# IRIS2_PCB_CPU.net
KiCad netlist of a schematic drawn in Altium Designer
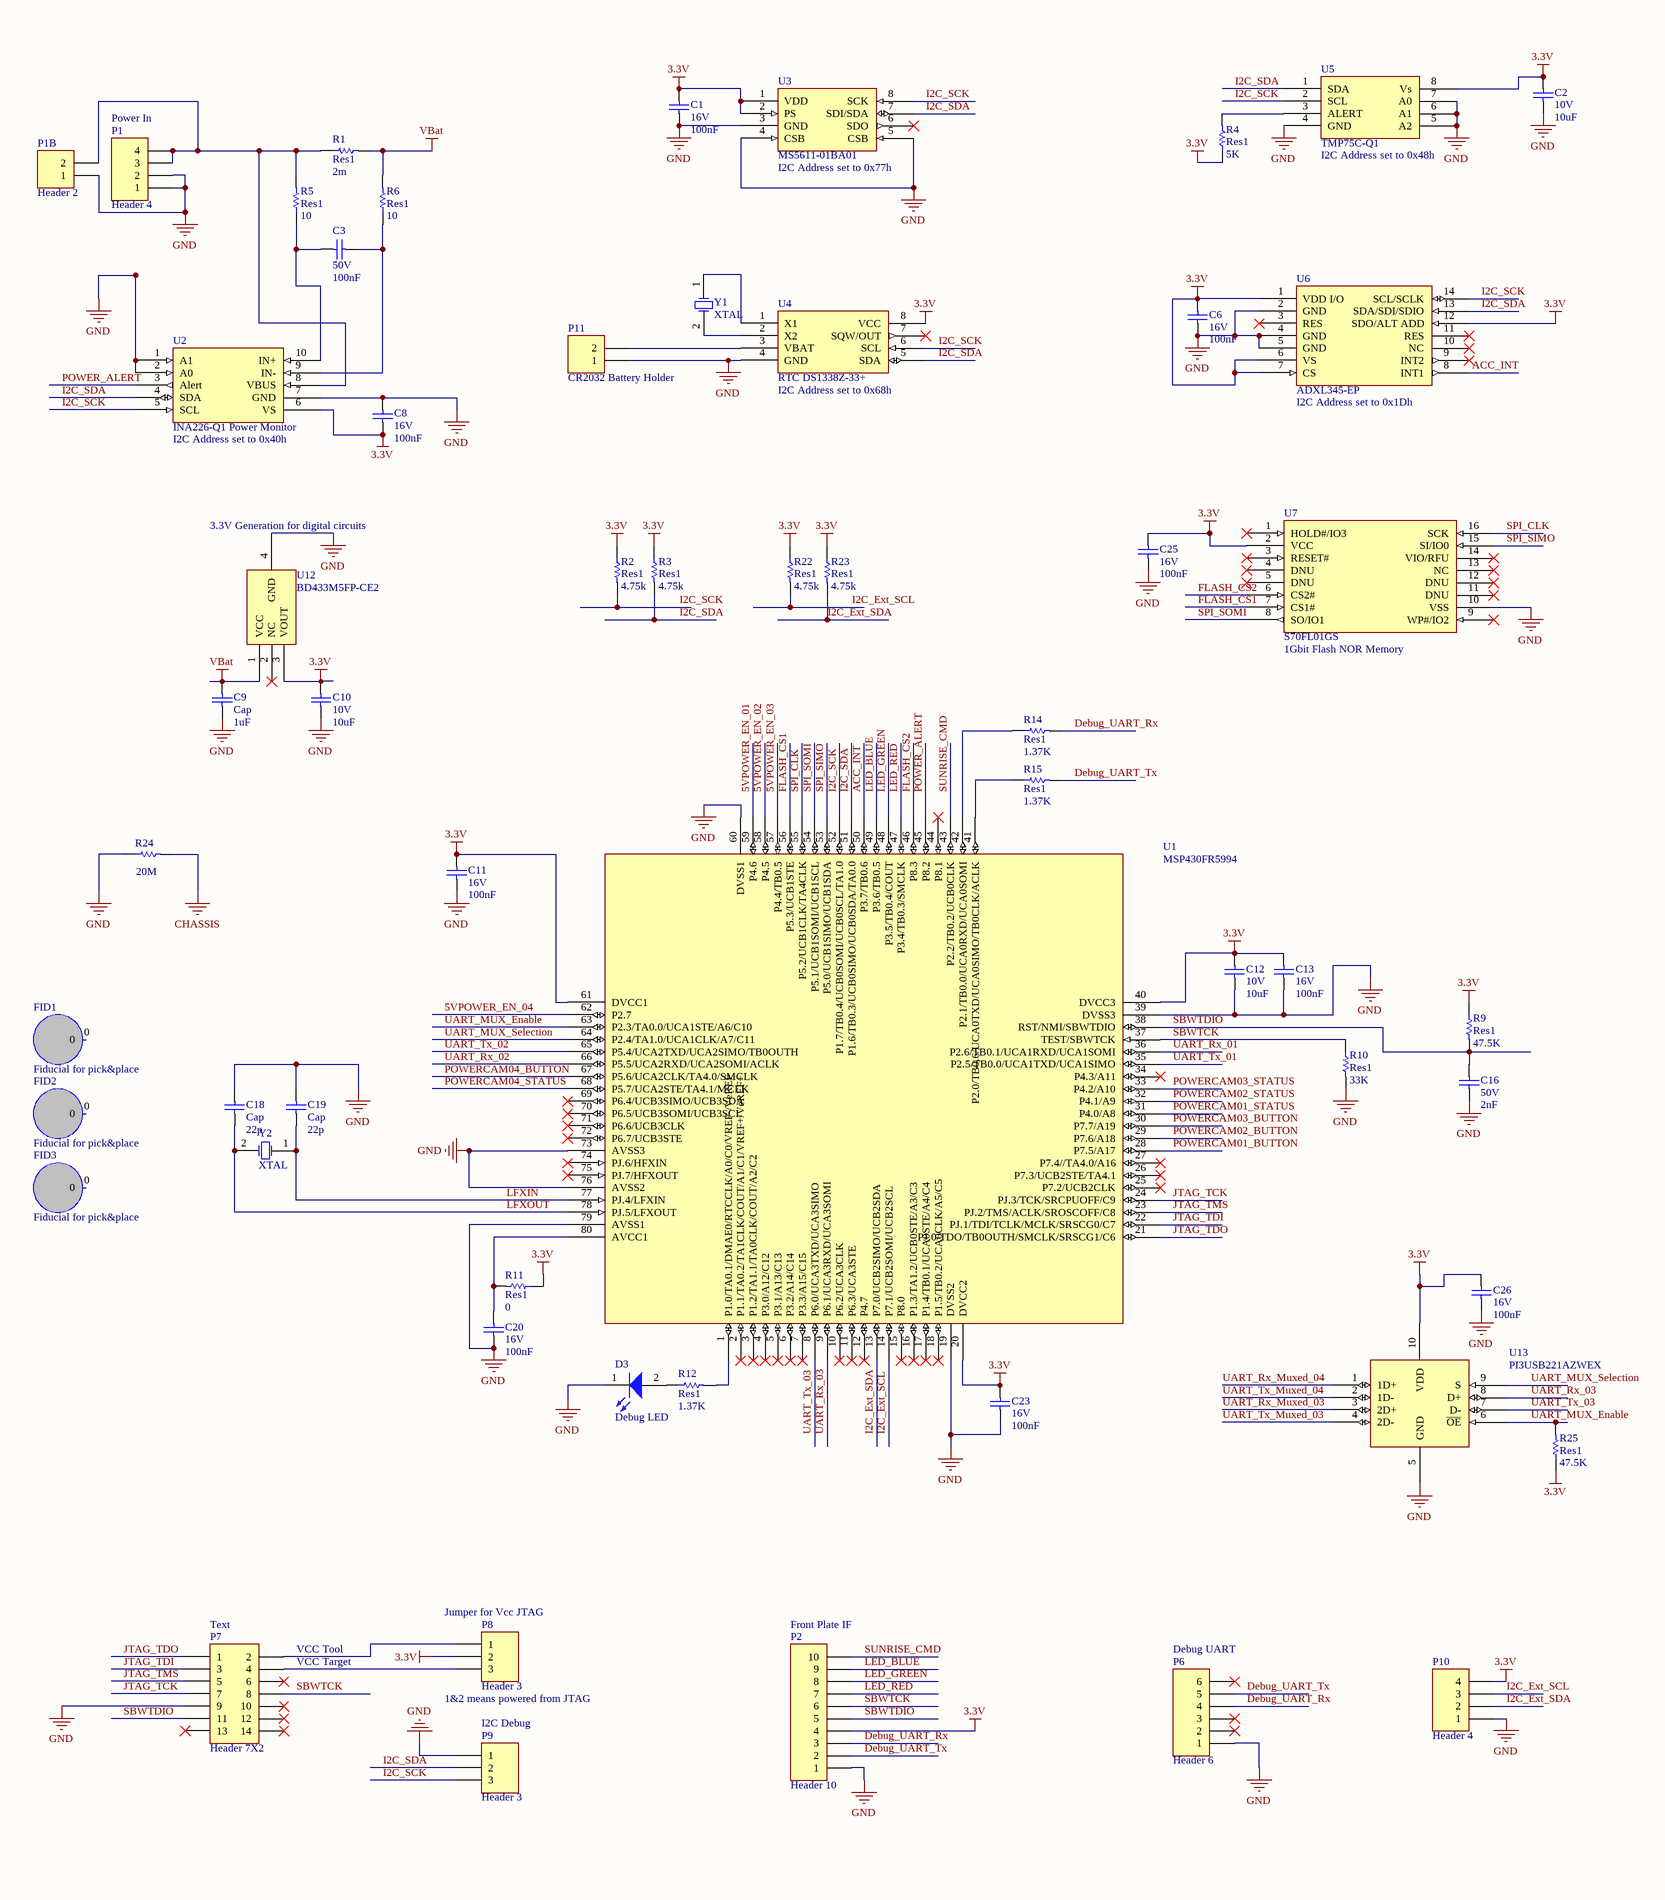
[diagram p0: IRIS2_PCB_CPU.SchDoc, left]
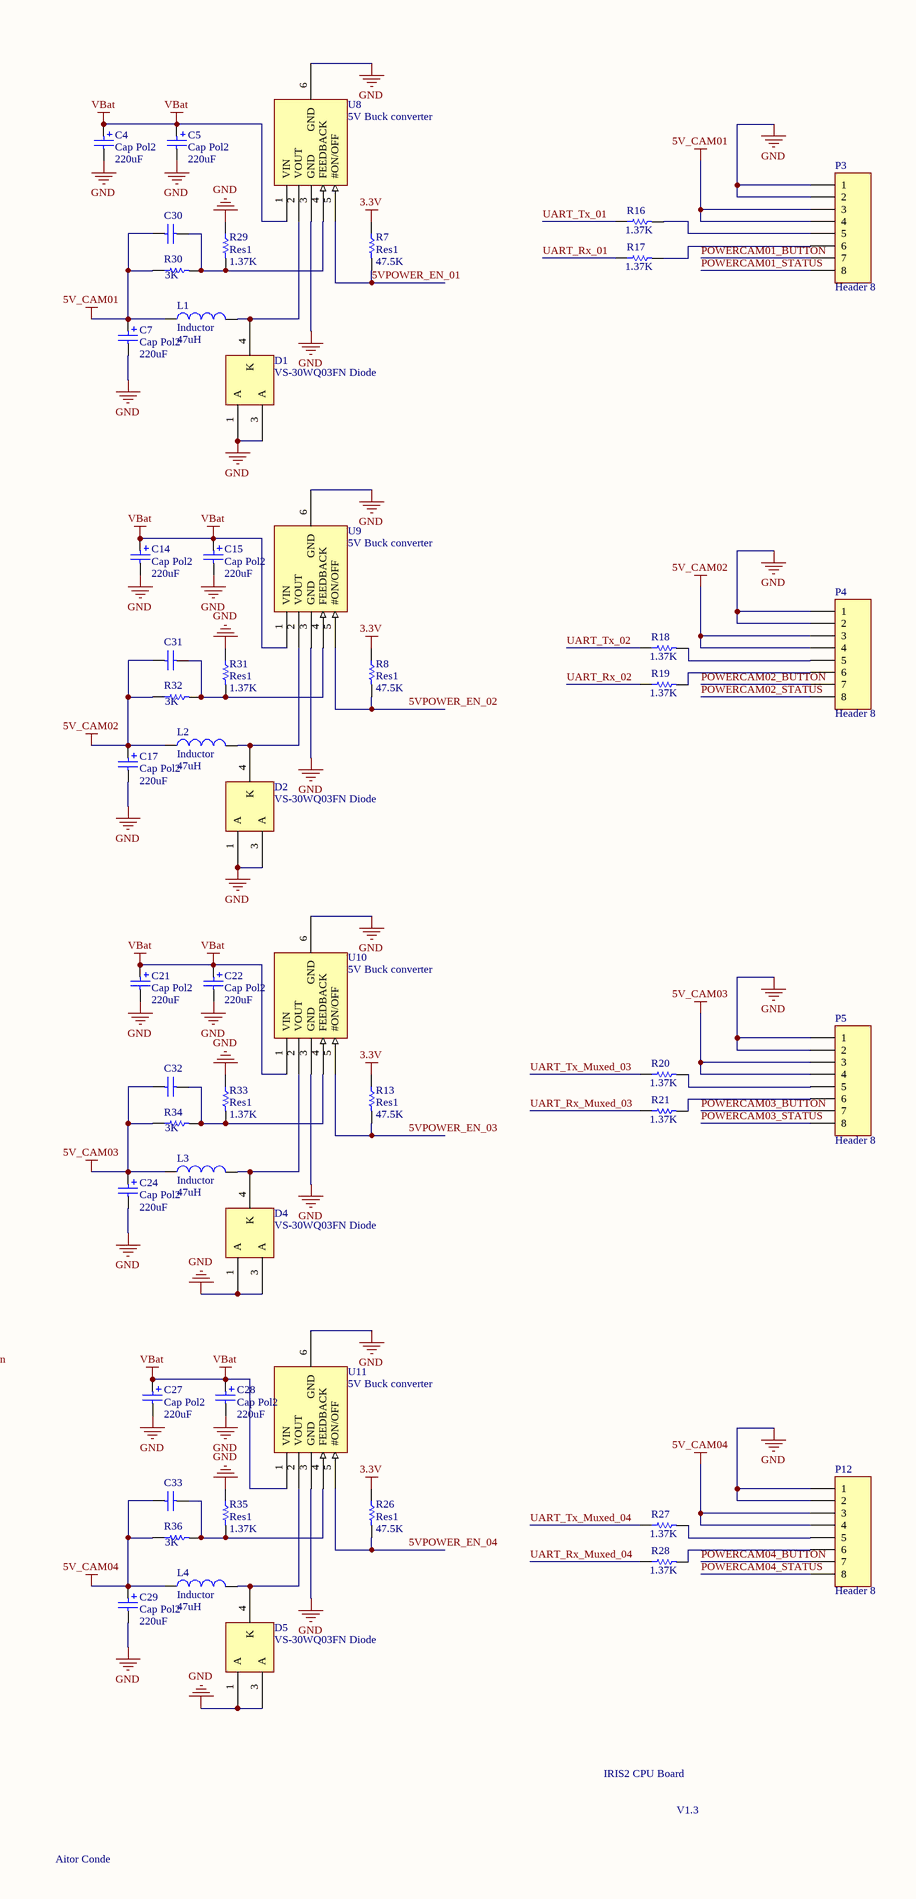
[diagram p1: IRIS2_PCB_CPU.SchDoc, right]

(export (version "E")
  (design (tool "Eeschema 10.0.6"))
  (components
    (comp (ref "C1")
      (value "16V")
      (footprint "0402")
      (description "Capacitor")
      (fields
        (field (name "ALTIUM_VALUE") "100nF")
        (field (name "MANUFACTURER") "Murata")
        (field (name "PUBLISHER") "Altium Limited")
      )
      (libsource (lib "Miscellaneous Devices") (part "Cap"))
    )
    (comp (ref "C2")
      (value "10V")
      (footprint "1608[0603]")
      (description "Capacitor")
      (fields
        (field (name "ALTIUM_VALUE") "10uF")
        (field (name "MANUFACTURER") "Murata")
        (field (name "PUBLISHER") "Altium Limited")
      )
      (libsource (lib "Miscellaneous Devices") (part "Cap"))
    )
    (comp (ref "C3")
      (value "50V")
      (footprint "6-0805_L")
      (description "Capacitor")
      (fields
        (field (name "ALTIUM_VALUE") "100nF")
        (field (name "MANUFACTURER") "Murata")
        (field (name "PUBLISHER") "Altium Limited")
      )
      (libsource (lib "Miscellaneous Devices") (part "Cap"))
    )
    (comp (ref "C4")
      (value "Cap Pol2")
      (footprint "2917 [7343 Metric]")
      (description "Polarized Capacitor (Axial)")
      (fields (field (name "ALTIUM_VALUE") "220uF") (field (name "MANUFACTURER") "Kemet"))
      (libsource (lib "Miscellaneous Devices") (part "Cap Pol2"))
    )
    (comp (ref "C5")
      (value "Cap Pol2")
      (footprint "2917 [7343 Metric]")
      (description "Polarized Capacitor (Axial)")
      (fields (field (name "ALTIUM_VALUE") "220uF") (field (name "MANUFACTURER") "Kemet"))
      (libsource (lib "Miscellaneous Devices") (part "Cap Pol2"))
    )
    (comp (ref "C6")
      (value "16V")
      (footprint "0402")
      (description "Capacitor")
      (fields
        (field (name "ALTIUM_VALUE") "100nF")
        (field (name "MANUFACTURER") "Murata")
        (field (name "PUBLISHER") "Altium Limited")
      )
      (libsource (lib "Miscellaneous Devices") (part "Cap"))
    )
    (comp (ref "C7")
      (value "Cap Pol2")
      (footprint "2917 [7343 Metric]")
      (description "Polarized Capacitor (Axial)")
      (fields (field (name "ALTIUM_VALUE") "220uF") (field (name "MANUFACTURER") "Kemet"))
      (libsource (lib "Miscellaneous Devices") (part "Cap Pol2"))
    )
    (comp (ref "C8")
      (value "16V")
      (footprint "0402")
      (description "Capacitor")
      (fields
        (field (name "ALTIUM_VALUE") "100nF")
        (field (name "MANUFACTURER") "Murata")
        (field (name "PUBLISHER") "Altium Limited")
      )
      (libsource (lib "Miscellaneous Devices") (part "Cap"))
    )
    (comp (ref "C9")
      (value "Cap")
      (footprint "1608[0603]")
      (description "Capacitor")
      (fields
        (field (name "MANUFACTURER") "Murata")
        (field (name "ALTIUM_VALUE") "1uF")
        (field (name "PUBLISHER") "Altium Limited")
      )
      (libsource (lib "Miscellaneous Devices") (part "Cap"))
    )
    (comp (ref "C10")
      (value "10V")
      (footprint "1608[0603]")
      (description "Capacitor")
      (fields
        (field (name "ALTIUM_VALUE") "10uF")
        (field (name "MANUFACTURER") "Murata")
        (field (name "PUBLISHER") "Altium Limited")
      )
      (libsource (lib "Miscellaneous Devices") (part "Cap"))
    )
    (comp (ref "C11")
      (value "16V")
      (footprint "0402")
      (description "Capacitor")
      (fields
        (field (name "ALTIUM_VALUE") "100nF")
        (field (name "MANUFACTURER") "Murata")
        (field (name "PUBLISHER") "Altium Limited")
      )
      (libsource (lib "Miscellaneous Devices") (part "Cap"))
    )
    (comp (ref "C12")
      (value "10V")
      (footprint "1608[0603]")
      (description "Capacitor")
      (fields
        (field (name "ALTIUM_VALUE") "10uF")
        (field (name "MANUFACTURER") "Murata")
        (field (name "PUBLISHER") "Altium Limited")
      )
      (libsource (lib "Miscellaneous Devices") (part "Cap"))
    )
    (comp (ref "C13")
      (value "16V")
      (footprint "0402")
      (description "Capacitor")
      (fields
        (field (name "ALTIUM_VALUE") "100nF")
        (field (name "MANUFACTURER") "Murata")
        (field (name "PUBLISHER") "Altium Limited")
      )
      (libsource (lib "Miscellaneous Devices") (part "Cap"))
    )
    (comp (ref "C14")
      (value "Cap Pol2")
      (footprint "2917 [7343 Metric]")
      (description "Polarized Capacitor (Axial)")
      (fields (field (name "ALTIUM_VALUE") "220uF") (field (name "MANUFACTURER") "Kemet"))
      (libsource (lib "Miscellaneous Devices") (part "Cap Pol2"))
    )
    (comp (ref "C15")
      (value "Cap Pol2")
      (footprint "2917 [7343 Metric]")
      (description "Polarized Capacitor (Axial)")
      (fields (field (name "ALTIUM_VALUE") "220uF") (field (name "MANUFACTURER") "Kemet"))
      (libsource (lib "Miscellaneous Devices") (part "Cap Pol2"))
    )
    (comp (ref "C16")
      (value "50V")
      (footprint "0402")
      (description "Capacitor")
      (fields
        (field (name "ALTIUM_VALUE") "2nF")
        (field (name "MANUFACTURER") "Murata")
        (field (name "PUBLISHER") "Altium Limited")
      )
      (libsource (lib "Miscellaneous Devices") (part "Cap"))
    )
    (comp (ref "C17")
      (value "Cap Pol2")
      (footprint "2917 [7343 Metric]")
      (description "Polarized Capacitor (Axial)")
      (fields (field (name "ALTIUM_VALUE") "220uF") (field (name "MANUFACTURER") "Kemet"))
      (libsource (lib "Miscellaneous Devices") (part "Cap Pol2"))
    )
    (comp (ref "C18")
      (value "Cap")
      (footprint "0402")
      (description "Capacitor")
      (fields
        (field (name "MANUFACTURER") "Murata")
        (field (name "ALTIUM_VALUE") "22p")
        (field (name "PUBLISHER") "Altium Limited")
      )
      (libsource (lib "Miscellaneous Devices") (part "Cap"))
    )
    (comp (ref "C19")
      (value "Cap")
      (footprint "0402")
      (description "Capacitor")
      (fields
        (field (name "MANUFACTURER") "Murata")
        (field (name "ALTIUM_VALUE") "22p")
        (field (name "PUBLISHER") "Altium Limited")
      )
      (libsource (lib "Miscellaneous Devices") (part "Cap"))
    )
    (comp (ref "C20")
      (value "16V")
      (footprint "0402")
      (description "Capacitor")
      (fields
        (field (name "ALTIUM_VALUE") "100nF")
        (field (name "MANUFACTURER") "Murata")
        (field (name "PUBLISHER") "Altium Limited")
      )
      (libsource (lib "Miscellaneous Devices") (part "Cap"))
    )
    (comp (ref "C21")
      (value "Cap Pol2")
      (footprint "2917 [7343 Metric]")
      (description "Polarized Capacitor (Axial)")
      (fields (field (name "ALTIUM_VALUE") "220uF") (field (name "MANUFACTURER") "Kemet"))
      (libsource (lib "Miscellaneous Devices") (part "Cap Pol2"))
    )
    (comp (ref "C22")
      (value "Cap Pol2")
      (footprint "2917 [7343 Metric]")
      (description "Polarized Capacitor (Axial)")
      (fields (field (name "ALTIUM_VALUE") "220uF") (field (name "MANUFACTURER") "Kemet"))
      (libsource (lib "Miscellaneous Devices") (part "Cap Pol2"))
    )
    (comp (ref "C23")
      (value "16V")
      (footprint "0402")
      (description "Capacitor")
      (fields
        (field (name "ALTIUM_VALUE") "100nF")
        (field (name "MANUFACTURER") "Murata")
        (field (name "PUBLISHER") "Altium Limited")
      )
      (libsource (lib "Miscellaneous Devices") (part "Cap"))
    )
    (comp (ref "C24")
      (value "Cap Pol2")
      (footprint "2917 [7343 Metric]")
      (description "Polarized Capacitor (Axial)")
      (fields (field (name "ALTIUM_VALUE") "220uF") (field (name "MANUFACTURER") "Kemet"))
      (libsource (lib "Miscellaneous Devices") (part "Cap Pol2"))
    )
    (comp (ref "C25")
      (value "16V")
      (footprint "0402")
      (description "Capacitor")
      (fields
        (field (name "ALTIUM_VALUE") "100nF")
        (field (name "MANUFACTURER") "Murata")
        (field (name "PUBLISHER") "Altium Limited")
      )
      (libsource (lib "Miscellaneous Devices") (part "Cap"))
    )
    (comp (ref "C26")
      (value "16V")
      (footprint "0402")
      (description "Capacitor")
      (fields
        (field (name "ALTIUM_VALUE") "100nF")
        (field (name "MANUFACTURER") "Murata")
        (field (name "PUBLISHER") "Altium Limited")
      )
      (libsource (lib "Miscellaneous Devices") (part "Cap"))
    )
    (comp (ref "C27")
      (value "Cap Pol2")
      (footprint "2917 [7343 Metric]")
      (description "Polarized Capacitor (Axial)")
      (fields (field (name "ALTIUM_VALUE") "220uF") (field (name "MANUFACTURER") "Kemet"))
      (libsource (lib "Miscellaneous Devices") (part "Cap Pol2"))
    )
    (comp (ref "C28")
      (value "Cap Pol2")
      (footprint "2917 [7343 Metric]")
      (description "Polarized Capacitor (Axial)")
      (fields (field (name "ALTIUM_VALUE") "220uF") (field (name "MANUFACTURER") "Kemet"))
      (libsource (lib "Miscellaneous Devices") (part "Cap Pol2"))
    )
    (comp (ref "C29")
      (value "Cap Pol2")
      (footprint "2917 [7343 Metric]")
      (description "Polarized Capacitor (Axial)")
      (fields (field (name "ALTIUM_VALUE") "220uF") (field (name "MANUFACTURER") "Kemet"))
      (libsource (lib "Miscellaneous Devices") (part "Cap Pol2"))
    )
    (comp (ref "C30")
      (value "16V")
      (footprint "0402")
      (description "Capacitor")
      (fields (field (name "PUBLISHER") "Altium Limited"))
      (libsource (lib "Miscellaneous Devices") (part "Cap"))
    )
    (comp (ref "C31")
      (value "16V")
      (footprint "0402")
      (description "Capacitor")
      (fields (field (name "PUBLISHER") "Altium Limited"))
      (libsource (lib "Miscellaneous Devices") (part "Cap"))
    )
    (comp (ref "C32")
      (value "16V")
      (footprint "0402")
      (description "Capacitor")
      (fields (field (name "PUBLISHER") "Altium Limited"))
      (libsource (lib "Miscellaneous Devices") (part "Cap"))
    )
    (comp (ref "C33")
      (value "16V")
      (footprint "0402")
      (description "Capacitor")
      (fields (field (name "PUBLISHER") "Altium Limited"))
      (libsource (lib "Miscellaneous Devices") (part "Cap"))
    )
    (comp (ref "D1")
      (value "VS-30WQ03FN Diode")
      (footprint "VS-30WQ03FN")
      (fields (field (name "MANUFACTURER") "Vishay"))
      (libsource (lib "Diode_VS-30WQ03FN") (part "VS-30WQ03FN"))
    )
    (comp (ref "D2")
      (value "VS-30WQ03FN Diode")
      (footprint "VS-30WQ03FN")
      (fields (field (name "MANUFACTURER") "Vishay"))
      (libsource (lib "Diode_VS-30WQ03FN") (part "VS-30WQ03FN"))
    )
    (comp (ref "D3")
      (value "Debug LED")
      (footprint "0402-A")
      (description "Typical RED, GREEN, YELLOW, AMBER GaAs LED")
      (fields (field (name "MANUFACTURER") "ROHM Semiconductor") (field (name "PUBLISHER") "Altium Limited"))
      (libsource (lib "Miscellaneous Devices") (part "LED2"))
    )
    (comp (ref "D4")
      (value "VS-30WQ03FN Diode")
      (footprint "VS-30WQ03FN")
      (fields (field (name "MANUFACTURER") "Vishay"))
      (libsource (lib "Diode_VS-30WQ03FN") (part "VS-30WQ03FN"))
    )
    (comp (ref "D5")
      (value "VS-30WQ03FN Diode")
      (footprint "VS-30WQ03FN")
      (fields (field (name "MANUFACTURER") "Vishay"))
      (libsource (lib "Diode_VS-30WQ03FN") (part "VS-30WQ03FN"))
    )
    (comp (ref "FID1")
      (value "Fiducial for pick&place")
      (footprint "FiducialPoint")
      (libsource (lib "FiducialPoint") (part "Fiducial"))
    )
    (comp (ref "FID2")
      (value "Fiducial for pick&place")
      (footprint "FiducialPoint")
      (libsource (lib "FiducialPoint") (part "Fiducial"))
    )
    (comp (ref "FID3")
      (value "Fiducial for pick&place")
      (footprint "FiducialPoint")
      (libsource (lib "FiducialPoint") (part "Fiducial"))
    )
    (comp (ref "L1")
      (value "Inductor")
      (footprint "DO5022P-473MLB")
      (fields (field (name "ALTIUM_VALUE") "47uH") (field (name "MANUFACTURER") "Coilcraft"))
      (libsource (lib "Miscellaneous Devices") (part "Inductor"))
    )
    (comp (ref "L2")
      (value "Inductor")
      (footprint "DO5022P-473MLB")
      (fields (field (name "ALTIUM_VALUE") "47uH") (field (name "MANUFACTURER") "Coilcraft"))
      (libsource (lib "Miscellaneous Devices") (part "Inductor"))
    )
    (comp (ref "L3")
      (value "Inductor")
      (footprint "DO5022P-473MLB")
      (fields (field (name "ALTIUM_VALUE") "47uH") (field (name "MANUFACTURER") "Coilcraft"))
      (libsource (lib "Miscellaneous Devices") (part "Inductor"))
    )
    (comp (ref "L4")
      (value "Inductor")
      (footprint "DO5022P-473MLB")
      (fields (field (name "ALTIUM_VALUE") "47uH") (field (name "MANUFACTURER") "Coilcraft"))
      (libsource (lib "Miscellaneous Devices") (part "Inductor"))
    )
    (comp (ref "P1")
      (value "Header 4")
      (footprint "53047-0410")
      (description "Header, 4-Pin")
      (fields (field (name "MANUFACTURER") "Molex") (field (name "PUBLISHER") "Altium Limited"))
      (libsource (lib "Miscellaneous Connectors") (part "Header 4"))
    )
    (comp (ref "P1B")
      (value "Header 2")
      (footprint "HDR1X2")
      (description "Header, 2-Pin")
      (fields (field (name "PUBLISHER") "Altium Limited"))
      (libsource (lib "Miscellaneous Connectors") (part "Header 2"))
    )
    (comp (ref "P2")
      (value "Header 10")
      (footprint "530471010")
      (description "Header, 10-Pin")
      (fields (field (name "MANUFACTURER") "Molex"))
      (libsource (lib "Miscellaneous Connectors") (part "Header 10"))
    )
    (comp (ref "P3")
      (value "Header 8")
      (footprint "0530470810")
      (description "Header, 8-Pin")
      (fields (field (name "MANUFACTURER") "Molex"))
      (libsource (lib "Miscellaneous Connectors") (part "Header 8"))
    )
    (comp (ref "P4")
      (value "Header 8")
      (footprint "0530470810")
      (description "Header, 8-Pin")
      (fields (field (name "MANUFACTURER") "Molex"))
      (libsource (lib "Miscellaneous Connectors") (part "Header 8"))
    )
    (comp (ref "P5")
      (value "Header 8")
      (footprint "0530470810")
      (description "Header, 8-Pin")
      (fields (field (name "MANUFACTURER") "Molex"))
      (libsource (lib "Miscellaneous Connectors") (part "Header 8"))
    )
    (comp (ref "P6")
      (value "Header 6")
      (footprint "HDR1X6")
      (description "Header, 6-Pin")
      (fields (field (name "PUBLISHER") "Altium Limited"))
      (libsource (lib "Miscellaneous Connectors") (part "Header 6"))
    )
    (comp (ref "P7")
      (value "Header 7X2")
      (footprint "HDR2X7")
      (description "Header, 7-Pin, Dual row")
      (fields (field (name "PUBLISHER") "Altium Limited"))
      (libsource (lib "Miscellaneous Connectors") (part "Header 7X2"))
    )
    (comp (ref "P8")
      (value "Header 3")
      (footprint "HDR1X3")
      (description "Header, 3-Pin")
      (fields (field (name "PUBLISHER") "Altium Limited"))
      (libsource (lib "Miscellaneous Connectors") (part "Header 3"))
    )
    (comp (ref "P9")
      (value "Header 3")
      (footprint "HDR1X3")
      (description "Header, 3-Pin")
      (fields (field (name "PUBLISHER") "Altium Limited"))
      (libsource (lib "Miscellaneous Connectors") (part "Header 3"))
    )
    (comp (ref "P10")
      (value "Header 4")
      (footprint "53047-0410")
      (description "Header, 4-Pin")
      (fields (field (name "MANUFACTURER") "Molex") (field (name "PUBLISHER") "Altium Limited"))
      (libsource (lib "Miscellaneous Connectors") (part "Header 4"))
    )
    (comp (ref "P11")
      (value "CR2032 Battery Holder")
      (footprint "SMTU2032-LF")
      (fields (field (name "MANUFACTURER") "Renata"))
      (libsource (lib "Miscellaneous Connectors") (part "Header 2"))
    )
    (comp (ref "P12")
      (value "Header 8")
      (footprint "0530470810")
      (description "Header, 8-Pin")
      (fields (field (name "MANUFACTURER") "Molex"))
      (libsource (lib "Miscellaneous Connectors") (part "Header 8"))
    )
    (comp (ref "R1")
      (value "Res1")
      (footprint "INDC3216")
      (description "Resistor")
      (fields
        (field (name "ALTIUM_VALUE") "2m")
        (field (name "MANUFACTURER") "ROHM Semiconductor")
        (field (name "SPPLIER PART NUMBER") "755-PMR18EZPFV2L00")
        (field (name "PUBLISHER") "Altium Limited")
      )
      (libsource (lib "Miscellaneous Devices") (part "Res1"))
    )
    (comp (ref "R2")
      (value "Res1")
      (footprint "0402")
      (description "Resistor")
      (fields
        (field (name "MANUFACTURER") "Panasonic")
        (field (name "ALTIUM_VALUE") "4.75k")
        (field (name "PUBLISHER") "Altium Limited")
      )
      (libsource (lib "Miscellaneous Devices") (part "Res1"))
    )
    (comp (ref "R3")
      (value "Res1")
      (footprint "0402")
      (description "Resistor")
      (fields
        (field (name "MANUFACTURER") "Panasonic")
        (field (name "ALTIUM_VALUE") "4.75k")
        (field (name "PUBLISHER") "Altium Limited")
      )
      (libsource (lib "Miscellaneous Devices") (part "Res1"))
    )
    (comp (ref "R4")
      (value "Res1")
      (footprint "0402")
      (description "Resistor")
      (fields
        (field (name "ALTIUM_VALUE") "5K")
        (field (name "MANUFACTURER") "Yageo")
        (field (name "PUBLISHER") "Altium Limited")
      )
      (libsource (lib "Miscellaneous Devices") (part "Res1"))
    )
    (comp (ref "R5")
      (value "Res1")
      (footprint "0402")
      (description "Resistor")
      (fields
        (field (name "MANUFACTURER") "Panasonic")
        (field (name "ALTIUM_VALUE") "10")
        (field (name "PUBLISHER") "Altium Limited")
      )
      (libsource (lib "Miscellaneous Devices") (part "Res1"))
    )
    (comp (ref "R6")
      (value "Res1")
      (footprint "0402")
      (description "Resistor")
      (fields
        (field (name "MANUFACTURER") "Panasonic")
        (field (name "ALTIUM_VALUE") "10")
        (field (name "PUBLISHER") "Altium Limited")
      )
      (libsource (lib "Miscellaneous Devices") (part "Res1"))
    )
    (comp (ref "R7")
      (value "Res1")
      (footprint "0402")
      (description "Resistor")
      (fields (field (name "ALTIUM_VALUE") "47.5K") (field (name "MANUFACTURER") "Panasonic"))
      (libsource (lib "Miscellaneous Devices") (part "Res1"))
    )
    (comp (ref "R8")
      (value "Res1")
      (footprint "0402")
      (description "Resistor")
      (fields (field (name "ALTIUM_VALUE") "47.5K") (field (name "MANUFACTURER") "Panasonic"))
      (libsource (lib "Miscellaneous Devices") (part "Res1"))
    )
    (comp (ref "R9")
      (value "Res1")
      (footprint "0402")
      (description "Resistor")
      (fields (field (name "ALTIUM_VALUE") "47.5K") (field (name "MANUFACTURER") "Panasonic"))
      (libsource (lib "Miscellaneous Devices") (part "Res1"))
    )
    (comp (ref "R10")
      (value "Res1")
      (footprint "0402")
      (description "Resistor")
      (fields
        (field (name "ALTIUM_VALUE") "33K")
        (field (name "MANUFACTURER") "Panasonic")
        (field (name "PUBLISHER") "Altium Limited")
      )
      (libsource (lib "Miscellaneous Devices") (part "Res1"))
    )
    (comp (ref "R11")
      (value "Res1")
      (footprint "J1-0603")
      (description "Resistor")
      (fields
        (field (name "ALTIUM_VALUE") "0")
        (field (name "MANUFACTURER") "Panasonic")
        (field (name "PUBLISHER") "Altium Limited")
      )
      (libsource (lib "Miscellaneous Devices") (part "Res1"))
    )
    (comp (ref "R12")
      (value "Res1")
      (footprint "0402")
      (description "Resistor")
      (fields
        (field (name "MANUFACTURER") "Panasonic")
        (field (name "ALTIUM_VALUE") "1.37K")
        (field (name "PUBLISHER") "Altium Limited")
      )
      (libsource (lib "Miscellaneous Devices") (part "Res1"))
    )
    (comp (ref "R13")
      (value "Res1")
      (footprint "0402")
      (description "Resistor")
      (fields (field (name "ALTIUM_VALUE") "47.5K") (field (name "MANUFACTURER") "Panasonic"))
      (libsource (lib "Miscellaneous Devices") (part "Res1"))
    )
    (comp (ref "R14")
      (value "Res1")
      (footprint "0402")
      (description "Resistor")
      (fields
        (field (name "MANUFACTURER") "Panasonic")
        (field (name "ALTIUM_VALUE") "1.37K")
        (field (name "PUBLISHER") "Altium Limited")
      )
      (libsource (lib "Miscellaneous Devices") (part "Res1"))
    )
    (comp (ref "R15")
      (value "Res1")
      (footprint "0402")
      (description "Resistor")
      (fields
        (field (name "MANUFACTURER") "Panasonic")
        (field (name "ALTIUM_VALUE") "1.37K")
        (field (name "PUBLISHER") "Altium Limited")
      )
      (libsource (lib "Miscellaneous Devices") (part "Res1"))
    )
    (comp (ref "R16")
      (value "1.37K")
      (footprint "0402")
      (description "Resistor")
      (fields
        (field (name "MANUFACTURER") "Panasonic")
        (field (name "Comment") "Res1")
        (field (name "PUBLISHER") "Altium Limited")
      )
      (libsource (lib "Miscellaneous Devices") (part "Res1"))
    )
    (comp (ref "R17")
      (value "1.37K")
      (footprint "0402")
      (description "Resistor")
      (fields
        (field (name "MANUFACTURER") "Panasonic")
        (field (name "Comment") "Res1")
        (field (name "PUBLISHER") "Altium Limited")
      )
      (libsource (lib "Miscellaneous Devices") (part "Res1"))
    )
    (comp (ref "R18")
      (value "1.37K")
      (footprint "0402")
      (description "Resistor")
      (fields
        (field (name "MANUFACTURER") "Panasonic")
        (field (name "Comment") "Res1")
        (field (name "PUBLISHER") "Altium Limited")
      )
      (libsource (lib "Miscellaneous Devices") (part "Res1"))
    )
    (comp (ref "R19")
      (value "1.37K")
      (footprint "0402")
      (description "Resistor")
      (fields
        (field (name "MANUFACTURER") "Panasonic")
        (field (name "Comment") "Res1")
        (field (name "PUBLISHER") "Altium Limited")
      )
      (libsource (lib "Miscellaneous Devices") (part "Res1"))
    )
    (comp (ref "R20")
      (value "1.37K")
      (footprint "0402")
      (description "Resistor")
      (fields
        (field (name "MANUFACTURER") "Panasonic")
        (field (name "Comment") "Res1")
        (field (name "PUBLISHER") "Altium Limited")
      )
      (libsource (lib "Miscellaneous Devices") (part "Res1"))
    )
    (comp (ref "R21")
      (value "1.37K")
      (footprint "0402")
      (description "Resistor")
      (fields
        (field (name "MANUFACTURER") "Panasonic")
        (field (name "Comment") "Res1")
        (field (name "PUBLISHER") "Altium Limited")
      )
      (libsource (lib "Miscellaneous Devices") (part "Res1"))
    )
    (comp (ref "R22")
      (value "Res1")
      (footprint "0402")
      (description "Resistor")
      (fields
        (field (name "MANUFACTURER") "Panasonic")
        (field (name "ALTIUM_VALUE") "4.75k")
        (field (name "PUBLISHER") "Altium Limited")
      )
      (libsource (lib "Miscellaneous Devices") (part "Res1"))
    )
    (comp (ref "R23")
      (value "Res1")
      (footprint "0402")
      (description "Resistor")
      (fields
        (field (name "MANUFACTURER") "Panasonic")
        (field (name "ALTIUM_VALUE") "4.75k")
        (field (name "PUBLISHER") "Altium Limited")
      )
      (libsource (lib "Miscellaneous Devices") (part "Res1"))
    )
    (comp (ref "R24")
      (value "20M")
      (footprint "6-0805_N")
      (description "Resistor")
      (fields
        (field (name "MANUFACTURER") "KOA")
        (field (name "Comment") "Res1")
        (field (name "PUBLISHER") "Altium Limited")
      )
      (libsource (lib "Miscellaneous Devices") (part "Res1"))
    )
    (comp (ref "R25")
      (value "Res1")
      (footprint "0402")
      (description "Resistor")
      (fields (field (name "ALTIUM_VALUE") "47.5K") (field (name "MANUFACTURER") "Panasonic"))
      (libsource (lib "Miscellaneous Devices") (part "Res1"))
    )
    (comp (ref "R26")
      (value "Res1")
      (footprint "0402")
      (description "Resistor")
      (fields (field (name "ALTIUM_VALUE") "47.5K") (field (name "MANUFACTURER") "Panasonic"))
      (libsource (lib "Miscellaneous Devices") (part "Res1"))
    )
    (comp (ref "R27")
      (value "1.37K")
      (footprint "0402")
      (description "Resistor")
      (fields
        (field (name "MANUFACTURER") "Panasonic")
        (field (name "Comment") "Res1")
        (field (name "PUBLISHER") "Altium Limited")
      )
      (libsource (lib "Miscellaneous Devices") (part "Res1"))
    )
    (comp (ref "R28")
      (value "1.37K")
      (footprint "0402")
      (description "Resistor")
      (fields
        (field (name "MANUFACTURER") "Panasonic")
        (field (name "Comment") "Res1")
        (field (name "PUBLISHER") "Altium Limited")
      )
      (libsource (lib "Miscellaneous Devices") (part "Res1"))
    )
    (comp (ref "R29")
      (value "Res1")
      (footprint "0402")
      (description "Resistor")
      (fields
        (field (name "MANUFACTURER") "Panasonic")
        (field (name "ALTIUM_VALUE") "1.37K")
        (field (name "PUBLISHER") "Altium Limited")
      )
      (libsource (lib "Miscellaneous Devices") (part "Res1"))
    )
    (comp (ref "R30")
      (value "3K")
      (footprint "0402")
      (description "Resistor")
      (fields
        (field (name "MANUFACTURER") "Vishay")
        (field (name "Comment") "Res1")
        (field (name "PUBLISHER") "Altium Limited")
      )
      (libsource (lib "Miscellaneous Devices") (part "Res1"))
    )
    (comp (ref "R31")
      (value "Res1")
      (footprint "0402")
      (description "Resistor")
      (fields
        (field (name "MANUFACTURER") "Panasonic")
        (field (name "ALTIUM_VALUE") "1.37K")
        (field (name "PUBLISHER") "Altium Limited")
      )
      (libsource (lib "Miscellaneous Devices") (part "Res1"))
    )
    (comp (ref "R32")
      (value "3K")
      (footprint "0402")
      (description "Resistor")
      (fields
        (field (name "MANUFACTURER") "Vishay")
        (field (name "Comment") "Res1")
        (field (name "PUBLISHER") "Altium Limited")
      )
      (libsource (lib "Miscellaneous Devices") (part "Res1"))
    )
    (comp (ref "R33")
      (value "Res1")
      (footprint "0402")
      (description "Resistor")
      (fields
        (field (name "MANUFACTURER") "Panasonic")
        (field (name "ALTIUM_VALUE") "1.37K")
        (field (name "PUBLISHER") "Altium Limited")
      )
      (libsource (lib "Miscellaneous Devices") (part "Res1"))
    )
    (comp (ref "R34")
      (value "3K")
      (footprint "0402")
      (description "Resistor")
      (fields
        (field (name "MANUFACTURER") "Vishay")
        (field (name "Comment") "Res1")
        (field (name "PUBLISHER") "Altium Limited")
      )
      (libsource (lib "Miscellaneous Devices") (part "Res1"))
    )
    (comp (ref "R35")
      (value "Res1")
      (footprint "0402")
      (description "Resistor")
      (fields
        (field (name "MANUFACTURER") "Panasonic")
        (field (name "ALTIUM_VALUE") "1.37K")
        (field (name "PUBLISHER") "Altium Limited")
      )
      (libsource (lib "Miscellaneous Devices") (part "Res1"))
    )
    (comp (ref "R36")
      (value "3K")
      (footprint "0402")
      (description "Resistor")
      (fields
        (field (name "MANUFACTURER") "Vishay")
        (field (name "Comment") "Res1")
        (field (name "PUBLISHER") "Altium Limited")
      )
      (libsource (lib "Miscellaneous Devices") (part "Res1"))
    )
    (comp (ref "U1")
      (value "MSP430FR5994")
      (footprint "MSP430FR59941PN")
      (description "MSP430FR5994, 80 pin MSP430 FRAM")
      (fields (field (name "MANUFACTURER") "Texas Instruments"))
      (libsource (lib "MSP430FR5994") (part "MSP430FR5994"))
    )
    (comp (ref "U2")
      (value "INA226-Q1 Power Monitor")
      (footprint "INA226-Q1")
      (description "Texas Instruments INA226-Q1 I2C temperature sensor INA226AQDGSRQ1")
      (fields (field (name "MANUFACTURER") "Texas Instruments"))
      (libsource (lib "INA226-Q1") (part "INA226-Q1"))
    )
    (comp (ref "U3")
      (value "MS5611-01BA01")
      (footprint "MS5611-01BA01")
      (description "MS5611-01BA01 Barometric Pressure Sensor")
      (fields (field (name "MANUFACTURER") "measurement specialties"))
      (libsource (lib "MS5611-01BA01") (part "MS5611-01BA01"))
    )
    (comp (ref "U4")
      (value "RTC DS1338Z-33+")
      (footprint "DS1338Z-33+")
      (description "RTC I2C DS1338Z-33+ SOIC-8")
      (fields (field (name "MANUFACTURER") "Maxim Integrated"))
      (libsource (lib "RTC_DS1338Z-33+") (part "DS1338Z-33+"))
    )
    (comp (ref "U5")
      (value "TMP75C-Q1")
      (footprint "TMP75C-Q1")
      (fields (field (name "MANUFACTURER") "Texas Instruments"))
      (libsource (lib "TMP75C-Q1") (part "TMP75C-Q1"))
    )
    (comp (ref "U6")
      (value "ADXL345-EP")
      (footprint "ADXL345-EP")
      (description "ADXL345-EP I2C Accelerometer")
      (fields (field (name "MANUFACTURER") "Analog Devices"))
      (libsource (lib "ADXL345-EP") (part "ADXL345-EP"))
    )
    (comp (ref "U7")
      (value "S70FL01GS")
      (footprint "SPIFlash_S70FL01GSAGMFV010")
      (description "S70FL01GS SPI NOR Flash")
      (fields (field (name "MANUFACTURER") "Cypress"))
      (libsource (lib "SPIFlash_S70FL01GSAGMFV010") (part "S70FL01GS"))
    )
    (comp (ref "U8")
      (value "5V Buck converter")
      (footprint "DPAK170P1435X457-6N")
      (description "LM2596S-5.0/NOPB 5V Buck converter")
      (fields (field (name "MANUFACTURER") "Texas Instruments"))
      (libsource (lib "LM2596S-5.0") (part "LM2596S-5.0/NOPB"))
    )
    (comp (ref "U9")
      (value "5V Buck converter")
      (footprint "DPAK170P1435X457-6N")
      (description "LM2596S-5.0/NOPB 5V Buck converter")
      (fields (field (name "MANUFACTURER") "Texas Instruments"))
      (libsource (lib "LM2596S-5.0") (part "LM2596S-5.0/NOPB"))
    )
    (comp (ref "U10")
      (value "5V Buck converter")
      (footprint "DPAK170P1435X457-6N")
      (description "LM2596S-5.0/NOPB 5V Buck converter")
      (fields (field (name "MANUFACTURER") "Texas Instruments"))
      (libsource (lib "LM2596S-5.0") (part "LM2596S-5.0/NOPB"))
    )
    (comp (ref "U11")
      (value "5V Buck converter")
      (footprint "DPAK170P1435X457-6N")
      (description "LM2596S-5.0/NOPB 5V Buck converter")
      (fields (field (name "MANUFACTURER") "Texas Instruments"))
      (libsource (lib "LM2596S-5.0") (part "LM2596S-5.0/NOPB"))
    )
    (comp (ref "U12")
      (value "BD433M5FP-CE2")
      (footprint "BD433M5FP-CE2")
      (description "BD433M5FP-CE2\r\nLDO 3.3V 500mV")
      (fields (field (name "MANUFACTURER") "ROHM Semiconductor"))
      (libsource (lib "BD433M5FP-CE2") (part "BD433M5FP-CE2"))
    )
    (comp (ref "U13")
      (value "PI3USB221AZWEX")
      (footprint "PI3USB221AZWEX")
      (description "PI3USB221AZWEX Multiplexer")
      (fields (field (name "MANUFACTURER") "Diodes Incorporated"))
      (libsource (lib "Mux_PI3USB221AZWEX") (part "PI3USB221AZWEX"))
    )
    (comp (ref "Y1")
      (value "XTAL")
      (footprint "XTAL_ECS-.327-9-34R-TR")
      (description "Crystal Oscillator")
      (fields (field (name "MANUFACTURER") "ECS"))
      (libsource (lib "Miscellaneous Devices") (part "XTAL"))
    )
    (comp (ref "Y2")
      (value "XTAL")
      (footprint "XTAL_ECS-.327-9-34R-TR")
      (description "Crystal Oscillator")
      (fields (field (name "MANUFACTURER") "ECS"))
      (libsource (lib "Miscellaneous Devices") (part "XTAL"))
    )
  )
  (nets
    (net (code "1") (name "/5VPOWER_EN_01") (class "Default")
      (node (ref "R7") (pin "2") (pinfunction "2_2") (pintype "passive"))
      (node (ref "U1") (pin "59") (pinfunction "P4.6_59") (pintype "bidirectional"))
      (node (ref "U8") (pin "5") (pinfunction "#ON/OFF_5") (pintype "input"))
    )
    (net (code "2") (name "/5VPOWER_EN_02") (class "Default")
      (node (ref "R8") (pin "2") (pinfunction "2_2") (pintype "passive"))
      (node (ref "U1") (pin "58") (pinfunction "P4.5_58") (pintype "bidirectional"))
      (node (ref "U9") (pin "5") (pinfunction "#ON/OFF_5") (pintype "input"))
    )
    (net (code "3") (name "/5VPOWER_EN_03") (class "Default")
      (node (ref "R13") (pin "2") (pinfunction "2_2") (pintype "passive"))
      (node (ref "U1") (pin "57") (pinfunction "P4.4/TB0.5_57") (pintype "bidirectional"))
      (node (ref "U10") (pin "5") (pinfunction "#ON/OFF_5") (pintype "input"))
    )
    (net (code "4") (name "/5VPOWER_EN_04") (class "Default")
      (node (ref "R26") (pin "2") (pinfunction "2_2") (pintype "passive"))
      (node (ref "U1") (pin "62") (pinfunction "P2.7_62") (pintype "bidirectional"))
      (node (ref "U11") (pin "5") (pinfunction "#ON/OFF_5") (pintype "input"))
    )
    (net (code "5") (name "/ACC_INT") (class "Default")
      (node (ref "U1") (pin "50") (pinfunction "P3.7/TB0.6_50") (pintype "bidirectional"))
      (node (ref "U6") (pin "8") (pinfunction "INT1_8") (pintype "output"))
    )
    (net (code "6") (name "/Debug_UART_Rx") (class "Default")
      (node (ref "P2") (pin "3") (pinfunction "3_3") (pintype "passive"))
      (node (ref "P6") (pin "4") (pinfunction "4_4") (pintype "passive"))
      (node (ref "R14") (pin "2") (pinfunction "2_2") (pintype "passive"))
    )
    (net (code "7") (name "/Debug_UART_Tx") (class "Default")
      (node (ref "P2") (pin "2") (pinfunction "2_2") (pintype "passive"))
      (node (ref "P6") (pin "5") (pinfunction "5_5") (pintype "passive"))
      (node (ref "R15") (pin "2") (pinfunction "2_2") (pintype "passive"))
    )
    (net (code "8") (name "/FLASH_CS1") (class "Default")
      (node (ref "U1") (pin "56") (pinfunction "P5.3/UCB1STE_56") (pintype "bidirectional"))
      (node (ref "U7") (pin "7") (pinfunction "CS1#_7") (pintype "input"))
    )
    (net (code "9") (name "/FLASH_CS2") (class "Default")
      (node (ref "U1") (pin "46") (pinfunction "P8.3_46") (pintype "bidirectional"))
      (node (ref "U7") (pin "6") (pinfunction "CS2#_6") (pintype "input"))
    )
    (net (code "10") (name "/I2C_Ext_SCL") (class "Default")
      (node (ref "P10") (pin "3") (pinfunction "3_3") (pintype "passive"))
      (node (ref "R22") (pin "2") (pinfunction "2_2") (pintype "passive"))
      (node (ref "U1") (pin "14") (pinfunction "P7.1/UCB2SOMI/UCB2SCL_14") (pintype "bidirectional"))
    )
    (net (code "11") (name "/I2C_Ext_SDA") (class "Default")
      (node (ref "P10") (pin "2") (pinfunction "2_2") (pintype "passive"))
      (node (ref "R23") (pin "2") (pinfunction "2_2") (pintype "passive"))
      (node (ref "U1") (pin "13") (pinfunction "P7.0/UCB2SIMO/UCB2SDA_13") (pintype "bidirectional"))
    )
    (net (code "12") (name "/I2C_SCK") (class "Default")
      (node (ref "P9") (pin "3") (pinfunction "3_3") (pintype "passive"))
      (node (ref "R2") (pin "2") (pinfunction "2_2") (pintype "passive"))
      (node (ref "U1") (pin "52") (pinfunction "P1.7/TB0.4/UCB0SOMI/UCB0SCL/TA1.0_52") (pintype "bidirectional"))
      (node (ref "U2") (pin "5") (pinfunction "SCL_5") (pintype "input"))
      (node (ref "U3") (pin "8") (pinfunction "SCK_8") (pintype "input"))
      (node (ref "U4") (pin "6") (pinfunction "SCL_6") (pintype "input"))
      (node (ref "U5") (pin "2") (pinfunction "SCL_2") (pintype "passive"))
      (node (ref "U6") (pin "14") (pinfunction "SCL/SCLK_14") (pintype "bidirectional"))
    )
    (net (code "13") (name "/I2C_SDA") (class "Default")
      (node (ref "P9") (pin "2") (pinfunction "2_2") (pintype "passive"))
      (node (ref "R3") (pin "2") (pinfunction "2_2") (pintype "passive"))
      (node (ref "U1") (pin "51") (pinfunction "P1.6/TB0.3/UCB0SIMO/UCB0SDA/TA0.0_51") (pintype "bidirectional"))
      (node (ref "U2") (pin "4") (pinfunction "SDA_4") (pintype "bidirectional"))
      (node (ref "U3") (pin "7") (pinfunction "SDI/SDA_7") (pintype "bidirectional"))
      (node (ref "U4") (pin "5") (pinfunction "SDA_5") (pintype "bidirectional"))
      (node (ref "U5") (pin "1") (pinfunction "SDA_1") (pintype "passive"))
      (node (ref "U6") (pin "13") (pinfunction "SDA/SDI/SDIO_13") (pintype "input"))
    )
    (net (code "14") (name "/JTAG_TCK") (class "Default")
      (node (ref "P7") (pin "7") (pinfunction "7_7") (pintype "passive"))
      (node (ref "U1") (pin "24") (pinfunction "PJ.3/TCK/SRCPUOFF/C9_24") (pintype "bidirectional"))
    )
    (net (code "15") (name "/JTAG_TDI") (class "Default")
      (node (ref "P7") (pin "3") (pinfunction "3_3") (pintype "passive"))
      (node (ref "U1") (pin "22") (pinfunction "PJ.1/TDI/TCLK/MCLK/SRSCG0/C7_22") (pintype "bidirectional"))
    )
    (net (code "16") (name "/JTAG_TDO") (class "Default")
      (node (ref "P7") (pin "1") (pinfunction "1_1") (pintype "passive"))
      (node (ref "U1") (pin "21") (pinfunction "PJ.0/TDO/TB0OUTH/SMCLK/SRSCG1/C6_21") (pintype "bidirectional"))
    )
    (net (code "17") (name "/JTAG_TMS") (class "Default")
      (node (ref "P7") (pin "5") (pinfunction "5_5") (pintype "passive"))
      (node (ref "U1") (pin "23") (pinfunction "PJ.2/TMS/ACLK/SROSCOFF/C8_23") (pintype "bidirectional"))
    )
    (net (code "18") (name "/LED_BLUE") (class "Default")
      (node (ref "P2") (pin "9") (pinfunction "9_9") (pintype "passive"))
      (node (ref "U1") (pin "49") (pinfunction "P3.6/TB0.5_49") (pintype "bidirectional"))
    )
    (net (code "19") (name "/LED_GREEN") (class "Default")
      (node (ref "P2") (pin "8") (pinfunction "8_8") (pintype "passive"))
      (node (ref "U1") (pin "48") (pinfunction "P3.5/TB0.4/COUT_48") (pintype "bidirectional"))
    )
    (net (code "20") (name "/LED_RED") (class "Default")
      (node (ref "P2") (pin "7") (pinfunction "7_7") (pintype "passive"))
      (node (ref "U1") (pin "47") (pinfunction "P3.4/TB0.3/SMCLK_47") (pintype "bidirectional"))
    )
    (net (code "21") (name "/LFXIN") (class "Default")
      (node (ref "C19") (pin "1") (pinfunction "1_1") (pintype "passive"))
      (node (ref "U1") (pin "77") (pinfunction "PJ.4/LFXIN_77") (pintype "input"))
      (node (ref "Y2") (pin "1") (pinfunction "OSC1_1") (pintype "passive"))
    )
    (net (code "22") (name "/LFXOUT") (class "Default")
      (node (ref "C18") (pin "1") (pinfunction "1_1") (pintype "passive"))
      (node (ref "U1") (pin "78") (pinfunction "PJ.5/LFXOUT_78") (pintype "input"))
      (node (ref "Y2") (pin "2") (pinfunction "OSC2_2") (pintype "passive"))
    )
    (net (code "23") (name "/POWERCAM01_BUTTON") (class "Default")
      (node (ref "P3") (pin "7") (pinfunction "7_7") (pintype "passive"))
      (node (ref "U1") (pin "28") (pinfunction "P7.5/A17_28") (pintype "bidirectional"))
    )
    (net (code "24") (name "/POWERCAM01_STATUS") (class "Default")
      (node (ref "P3") (pin "8") (pinfunction "8_8") (pintype "passive"))
      (node (ref "U1") (pin "31") (pinfunction "P4.0/A8_31") (pintype "bidirectional"))
    )
    (net (code "25") (name "/POWERCAM02_BUTTON") (class "Default")
      (node (ref "P4") (pin "7") (pinfunction "7_7") (pintype "passive"))
      (node (ref "U1") (pin "29") (pinfunction "P7.6/A18_29") (pintype "bidirectional"))
    )
    (net (code "26") (name "/POWERCAM02_STATUS") (class "Default")
      (node (ref "P4") (pin "8") (pinfunction "8_8") (pintype "passive"))
      (node (ref "U1") (pin "32") (pinfunction "P4.1/A9_32") (pintype "bidirectional"))
    )
    (net (code "27") (name "/POWERCAM03_BUTTON") (class "Default")
      (node (ref "P5") (pin "7") (pinfunction "7_7") (pintype "passive"))
      (node (ref "U1") (pin "30") (pinfunction "P7.7/A19_30") (pintype "bidirectional"))
    )
    (net (code "28") (name "/POWERCAM03_STATUS") (class "Default")
      (node (ref "P5") (pin "8") (pinfunction "8_8") (pintype "passive"))
      (node (ref "U1") (pin "33") (pinfunction "P4.2/A10_33") (pintype "bidirectional"))
    )
    (net (code "29") (name "/POWERCAM04_BUTTON") (class "Default")
      (node (ref "P12") (pin "7") (pinfunction "7_7") (pintype "passive"))
      (node (ref "U1") (pin "67") (pinfunction "P5.6/UCA2CLK/TA4.0/SMCLK_67") (pintype "bidirectional"))
    )
    (net (code "30") (name "/POWERCAM04_STATUS") (class "Default")
      (node (ref "P12") (pin "8") (pinfunction "8_8") (pintype "passive"))
      (node (ref "U1") (pin "68") (pinfunction "P5.7/UCA2STE/TA4.1/MCLK_68") (pintype "bidirectional"))
    )
    (net (code "31") (name "/POWER_ALERT") (class "Default")
      (node (ref "U1") (pin "45") (pinfunction "P8.2_45") (pintype "bidirectional"))
      (node (ref "U2") (pin "3") (pinfunction "Alert_3") (pintype "output"))
    )
    (net (code "32") (name "/SBWTCK") (class "Default")
      (node (ref "P2") (pin "6") (pinfunction "6_6") (pintype "passive"))
      (node (ref "P7") (pin "8") (pinfunction "8_8") (pintype "passive"))
      (node (ref "R10") (pin "1") (pinfunction "1_1") (pintype "passive"))
      (node (ref "U1") (pin "37") (pinfunction "TEST/SBWTCK_37") (pintype "input"))
    )
    (net (code "33") (name "/SBWTDIO") (class "Default")
      (node (ref "C16") (pin "1") (pinfunction "1_1") (pintype "passive"))
      (node (ref "P2") (pin "5") (pinfunction "5_5") (pintype "passive"))
      (node (ref "P7") (pin "11") (pinfunction "11_11") (pintype "passive"))
      (node (ref "R9") (pin "2") (pinfunction "2_2") (pintype "passive"))
      (node (ref "U1") (pin "38") (pinfunction "RST/NMI/SBWTDIO_38") (pintype "bidirectional"))
    )
    (net (code "34") (name "/SPI_CLK") (class "Default")
      (node (ref "U1") (pin "55") (pinfunction "P5.2/UCB1CLK/TA4CLK_55") (pintype "bidirectional"))
      (node (ref "U7") (pin "16") (pinfunction "SCK_16") (pintype "input"))
    )
    (net (code "35") (name "/SPI_SIMO") (class "Default")
      (node (ref "U1") (pin "53") (pinfunction "P5.0/UCB1SIMO/UCB1SDA_53") (pintype "bidirectional"))
      (node (ref "U7") (pin "15") (pinfunction "SI/IO0_15") (pintype "input"))
    )
    (net (code "36") (name "/SPI_SOMI") (class "Default")
      (node (ref "U1") (pin "54") (pinfunction "P5.1/UCB1SOMI/UCB1SCL_54") (pintype "bidirectional"))
      (node (ref "U7") (pin "8") (pinfunction "SO/IO1_8") (pintype "output"))
    )
    (net (code "37") (name "/SUNRISE_CMD") (class "Default")
      (node (ref "P2") (pin "10") (pinfunction "10_10") (pintype "passive"))
      (node (ref "U1") (pin "43") (pinfunction "P2.2/TB0.2/UCB0CLK_43") (pintype "bidirectional"))
    )
    (net (code "38") (name "/UART_MUX_Enable") (class "Default")
      (node (ref "R25") (pin "2") (pinfunction "2_2") (pintype "passive"))
      (node (ref "U1") (pin "63") (pinfunction "P2.3/TA0.0/UCA1STE/A6/C10_63") (pintype "bidirectional"))
      (node (ref "U13") (pin "6") (pinfunction "~{OE}_6") (pintype "input"))
    )
    (net (code "39") (name "/UART_MUX_Selection") (class "Default")
      (node (ref "U1") (pin "64") (pinfunction "P2.4/TA1.0/UCA1CLK/A7/C11_64") (pintype "bidirectional"))
      (node (ref "U13") (pin "9") (pinfunction "S_9") (pintype "input"))
    )
    (net (code "40") (name "/UART_Rx_01") (class "Default")
      (node (ref "R17") (pin "1") (pinfunction "1_1") (pintype "passive"))
      (node (ref "U1") (pin "36") (pinfunction "P2.6/TB0.1/UCA1RXD/UCA1SOMI_36") (pintype "bidirectional"))
    )
    (net (code "41") (name "/UART_Rx_02") (class "Default")
      (node (ref "R19") (pin "1") (pinfunction "1_1") (pintype "passive"))
      (node (ref "U1") (pin "66") (pinfunction "P5.5/UCA2RXD/UCA2SOMI/ACLK_66") (pintype "bidirectional"))
    )
    (net (code "42") (name "/UART_Rx_03") (class "Default")
      (node (ref "U1") (pin "9") (pinfunction "P6.1/UCA3RXD/UCA3SOMI_9") (pintype "bidirectional"))
      (node (ref "U13") (pin "8") (pinfunction "D+_8") (pintype "bidirectional"))
    )
    (net (code "43") (name "/UART_Rx_Muxed_03") (class "Default")
      (node (ref "R21") (pin "1") (pinfunction "1_1") (pintype "passive"))
      (node (ref "U13") (pin "3") (pinfunction "2D+_3") (pintype "bidirectional"))
    )
    (net (code "44") (name "/UART_Rx_Muxed_04") (class "Default")
      (node (ref "R28") (pin "1") (pinfunction "1_1") (pintype "passive"))
      (node (ref "U13") (pin "1") (pinfunction "1D+_1") (pintype "bidirectional"))
    )
    (net (code "45") (name "/UART_Tx_01") (class "Default")
      (node (ref "R16") (pin "1") (pinfunction "1_1") (pintype "passive"))
      (node (ref "U1") (pin "35") (pinfunction "P2.5/TB0.0/UCA1TXD/UCA1SIMO_35") (pintype "bidirectional"))
    )
    (net (code "46") (name "/UART_Tx_02") (class "Default")
      (node (ref "R18") (pin "1") (pinfunction "1_1") (pintype "passive"))
      (node (ref "U1") (pin "65") (pinfunction "P5.4/UCA2TXD/UCA2SIMO/TB0OUTH_65") (pintype "bidirectional"))
    )
    (net (code "47") (name "/UART_Tx_03") (class "Default")
      (node (ref "U1") (pin "8") (pinfunction "P6.0/UCA3TXD/UCA3SIMO_8") (pintype "bidirectional"))
      (node (ref "U13") (pin "7") (pinfunction "D-_7") (pintype "bidirectional"))
    )
    (net (code "48") (name "/UART_Tx_Muxed_03") (class "Default")
      (node (ref "R20") (pin "1") (pinfunction "1_1") (pintype "passive"))
      (node (ref "U13") (pin "4") (pinfunction "2D-_4") (pintype "bidirectional"))
    )
    (net (code "49") (name "/UART_Tx_Muxed_04") (class "Default")
      (node (ref "R27") (pin "1") (pinfunction "1_1") (pintype "passive"))
      (node (ref "U13") (pin "2") (pinfunction "1D-_2") (pintype "bidirectional"))
    )
    (net (code "50") (name "3.3V") (class "Default")
      (node (ref "C1") (pin "1") (pinfunction "1_1") (pintype "passive"))
      (node (ref "C10") (pin "1") (pinfunction "1_1") (pintype "passive"))
      (node (ref "C11") (pin "1") (pinfunction "1_1") (pintype "passive"))
      (node (ref "C12") (pin "1") (pinfunction "1_1") (pintype "passive"))
      (node (ref "C13") (pin "1") (pinfunction "1_1") (pintype "passive"))
      (node (ref "C2") (pin "1") (pinfunction "1_1") (pintype "passive"))
      (node (ref "C23") (pin "1") (pinfunction "1_1") (pintype "passive"))
      (node (ref "C25") (pin "1") (pinfunction "1_1") (pintype "passive"))
      (node (ref "C26") (pin "1") (pinfunction "1_1") (pintype "passive"))
      (node (ref "C6") (pin "1") (pinfunction "1_1") (pintype "passive"))
      (node (ref "C8") (pin "2") (pinfunction "2_2") (pintype "passive"))
      (node (ref "P10") (pin "4") (pinfunction "4_4") (pintype "passive"))
      (node (ref "P2") (pin "4") (pinfunction "4_4") (pintype "passive"))
      (node (ref "P8") (pin "2") (pinfunction "2_2") (pintype "passive"))
      (node (ref "R11") (pin "1") (pinfunction "1_1") (pintype "passive"))
      (node (ref "R13") (pin "1") (pinfunction "1_1") (pintype "passive"))
      (node (ref "R2") (pin "1") (pinfunction "1_1") (pintype "passive"))
      (node (ref "R22") (pin "1") (pinfunction "1_1") (pintype "passive"))
      (node (ref "R23") (pin "1") (pinfunction "1_1") (pintype "passive"))
      (node (ref "R25") (pin "1") (pinfunction "1_1") (pintype "passive"))
      (node (ref "R26") (pin "1") (pinfunction "1_1") (pintype "passive"))
      (node (ref "R3") (pin "1") (pinfunction "1_1") (pintype "passive"))
      (node (ref "R4") (pin "1") (pinfunction "1_1") (pintype "passive"))
      (node (ref "R7") (pin "1") (pinfunction "1_1") (pintype "passive"))
      (node (ref "R8") (pin "1") (pinfunction "1_1") (pintype "passive"))
      (node (ref "R9") (pin "1") (pinfunction "1_1") (pintype "passive"))
      (node (ref "U1") (pin "20") (pinfunction "DVCC2_20") (pintype "power_in"))
      (node (ref "U1") (pin "40") (pinfunction "DVCC3_40") (pintype "power_in"))
      (node (ref "U1") (pin "61") (pinfunction "DVCC1_61") (pintype "power_in"))
      (node (ref "U12") (pin "3") (pinfunction "VOUT_3") (pintype "passive"))
      (node (ref "U13") (pin "10") (pinfunction "VDD_10") (pintype "power_in"))
      (node (ref "U2") (pin "6") (pinfunction "VS_6") (pintype "power_in"))
      (node (ref "U3") (pin "1") (pinfunction "VDD_1") (pintype "power_in"))
      (node (ref "U3") (pin "2") (pinfunction "PS_2") (pintype "input"))
      (node (ref "U4") (pin "8") (pinfunction "VCC_8") (pintype "power_in"))
      (node (ref "U5") (pin "8") (pinfunction "Vs_8") (pintype "passive"))
      (node (ref "U6") (pin "1") (pinfunction "VDD_I/O_1") (pintype "power_in"))
      (node (ref "U6") (pin "12") (pinfunction "SDO/ALT_ADD_12") (pintype "input"))
      (node (ref "U6") (pin "6") (pinfunction "VS_6") (pintype "power_in"))
      (node (ref "U6") (pin "7") (pinfunction "CS_7") (pintype "input"))
      (node (ref "U7") (pin "2") (pinfunction "VCC_2") (pintype "power_in"))
    )
    (net (code "51") (name "5V_CAM01") (class "Default")
      (node (ref "C30") (pin "1") (pinfunction "1_1") (pintype "passive"))
      (node (ref "C7") (pin "1") (pinfunction "1_1") (pintype "passive"))
      (node (ref "L1") (pin "1") (pinfunction "1_1") (pintype "passive"))
      (node (ref "P3") (pin "3") (pinfunction "3_3") (pintype "passive"))
      (node (ref "P3") (pin "4") (pinfunction "4_4") (pintype "passive"))
      (node (ref "R30") (pin "1") (pinfunction "1_1") (pintype "passive"))
    )
    (net (code "52") (name "5V_CAM02") (class "Default")
      (node (ref "C17") (pin "1") (pinfunction "1_1") (pintype "passive"))
      (node (ref "C31") (pin "1") (pinfunction "1_1") (pintype "passive"))
      (node (ref "L2") (pin "1") (pinfunction "1_1") (pintype "passive"))
      (node (ref "P4") (pin "3") (pinfunction "3_3") (pintype "passive"))
      (node (ref "P4") (pin "4") (pinfunction "4_4") (pintype "passive"))
      (node (ref "R32") (pin "1") (pinfunction "1_1") (pintype "passive"))
    )
    (net (code "53") (name "5V_CAM03") (class "Default")
      (node (ref "C24") (pin "1") (pinfunction "1_1") (pintype "passive"))
      (node (ref "C32") (pin "1") (pinfunction "1_1") (pintype "passive"))
      (node (ref "L3") (pin "1") (pinfunction "1_1") (pintype "passive"))
      (node (ref "P5") (pin "3") (pinfunction "3_3") (pintype "passive"))
      (node (ref "P5") (pin "4") (pinfunction "4_4") (pintype "passive"))
      (node (ref "R34") (pin "1") (pinfunction "1_1") (pintype "passive"))
    )
    (net (code "54") (name "5V_CAM04") (class "Default")
      (node (ref "C29") (pin "1") (pinfunction "1_1") (pintype "passive"))
      (node (ref "C33") (pin "1") (pinfunction "1_1") (pintype "passive"))
      (node (ref "L4") (pin "1") (pinfunction "1_1") (pintype "passive"))
      (node (ref "P12") (pin "3") (pinfunction "3_3") (pintype "passive"))
      (node (ref "P12") (pin "4") (pinfunction "4_4") (pintype "passive"))
      (node (ref "R36") (pin "1") (pinfunction "1_1") (pintype "passive"))
    )
    (net (code "55") (name "CHASSIS") (class "Default")
      (node (ref "R24") (pin "2") (pinfunction "2_2") (pintype "passive"))
    )
    (net (code "56") (name "GND") (class "Default")
      (node (ref "C1") (pin "2") (pinfunction "2_2") (pintype "passive"))
      (node (ref "C10") (pin "2") (pinfunction "2_2") (pintype "passive"))
      (node (ref "C11") (pin "2") (pinfunction "2_2") (pintype "passive"))
      (node (ref "C12") (pin "2") (pinfunction "2_2") (pintype "passive"))
      (node (ref "C13") (pin "2") (pinfunction "2_2") (pintype "passive"))
      (node (ref "C14") (pin "2") (pinfunction "2_2") (pintype "passive"))
      (node (ref "C15") (pin "2") (pinfunction "2_2") (pintype "passive"))
      (node (ref "C16") (pin "2") (pinfunction "2_2") (pintype "passive"))
      (node (ref "C17") (pin "2") (pinfunction "2_2") (pintype "passive"))
      (node (ref "C18") (pin "2") (pinfunction "2_2") (pintype "passive"))
      (node (ref "C19") (pin "2") (pinfunction "2_2") (pintype "passive"))
      (node (ref "C2") (pin "2") (pinfunction "2_2") (pintype "passive"))
      (node (ref "C20") (pin "2") (pinfunction "2_2") (pintype "passive"))
      (node (ref "C21") (pin "2") (pinfunction "2_2") (pintype "passive"))
      (node (ref "C22") (pin "2") (pinfunction "2_2") (pintype "passive"))
      (node (ref "C23") (pin "2") (pinfunction "2_2") (pintype "passive"))
      (node (ref "C24") (pin "2") (pinfunction "2_2") (pintype "passive"))
      (node (ref "C25") (pin "2") (pinfunction "2_2") (pintype "passive"))
      (node (ref "C26") (pin "2") (pinfunction "2_2") (pintype "passive"))
      (node (ref "C27") (pin "2") (pinfunction "2_2") (pintype "passive"))
      (node (ref "C28") (pin "2") (pinfunction "2_2") (pintype "passive"))
      (node (ref "C29") (pin "2") (pinfunction "2_2") (pintype "passive"))
      (node (ref "C4") (pin "2") (pinfunction "2_2") (pintype "passive"))
      (node (ref "C5") (pin "2") (pinfunction "2_2") (pintype "passive"))
      (node (ref "C6") (pin "2") (pinfunction "2_2") (pintype "passive"))
      (node (ref "C7") (pin "2") (pinfunction "2_2") (pintype "passive"))
      (node (ref "C8") (pin "1") (pinfunction "1_1") (pintype "passive"))
      (node (ref "C9") (pin "1") (pinfunction "1_1") (pintype "passive"))
      (node (ref "D1") (pin "1") (pinfunction "A_1") (pintype "passive"))
      (node (ref "D1") (pin "3") (pinfunction "A_3") (pintype "passive"))
      (node (ref "D2") (pin "1") (pinfunction "A_1") (pintype "passive"))
      (node (ref "D2") (pin "3") (pinfunction "A_3") (pintype "passive"))
      (node (ref "D3") (pin "1") (pinfunction "K_1") (pintype "passive"))
      (node (ref "D4") (pin "1") (pinfunction "A_1") (pintype "passive"))
      (node (ref "D4") (pin "3") (pinfunction "A_3") (pintype "passive"))
      (node (ref "D5") (pin "1") (pinfunction "A_1") (pintype "passive"))
      (node (ref "D5") (pin "3") (pinfunction "A_3") (pintype "passive"))
      (node (ref "P1") (pin "1") (pinfunction "1_1") (pintype "passive"))
      (node (ref "P1") (pin "2") (pinfunction "2_2") (pintype "passive"))
      (node (ref "P10") (pin "1") (pinfunction "1_1") (pintype "passive"))
      (node (ref "P11") (pin "1") (pinfunction "1_1") (pintype "passive"))
      (node (ref "P12") (pin "1") (pinfunction "1_1") (pintype "passive"))
      (node (ref "P12") (pin "2") (pinfunction "2_2") (pintype "passive"))
      (node (ref "P1B") (pin "1") (pinfunction "1_1") (pintype "passive"))
      (node (ref "P2") (pin "1") (pinfunction "1_1") (pintype "passive"))
      (node (ref "P3") (pin "1") (pinfunction "1_1") (pintype "passive"))
      (node (ref "P3") (pin "2") (pinfunction "2_2") (pintype "passive"))
      (node (ref "P4") (pin "1") (pinfunction "1_1") (pintype "passive"))
      (node (ref "P4") (pin "2") (pinfunction "2_2") (pintype "passive"))
      (node (ref "P5") (pin "1") (pinfunction "1_1") (pintype "passive"))
      (node (ref "P5") (pin "2") (pinfunction "2_2") (pintype "passive"))
      (node (ref "P6") (pin "1") (pinfunction "1_1") (pintype "passive"))
      (node (ref "P7") (pin "9") (pinfunction "9_9") (pintype "passive"))
      (node (ref "P9") (pin "1") (pinfunction "1_1") (pintype "passive"))
      (node (ref "R10") (pin "2") (pinfunction "2_2") (pintype "passive"))
      (node (ref "R24") (pin "1") (pinfunction "1_1") (pintype "passive"))
      (node (ref "R29") (pin "1") (pinfunction "1_1") (pintype "passive"))
      (node (ref "R31") (pin "1") (pinfunction "1_1") (pintype "passive"))
      (node (ref "R33") (pin "1") (pinfunction "1_1") (pintype "passive"))
      (node (ref "R35") (pin "1") (pinfunction "1_1") (pintype "passive"))
      (node (ref "U1") (pin "19") (pinfunction "DVSS2_19") (pintype "power_in"))
      (node (ref "U1") (pin "39") (pinfunction "DVSS3_39") (pintype "power_in"))
      (node (ref "U1") (pin "60") (pinfunction "DVSS1_60") (pintype "power_in"))
      (node (ref "U1") (pin "73") (pinfunction "AVSS3_73") (pintype "power_in"))
      (node (ref "U1") (pin "76") (pinfunction "AVSS2_76") (pintype "power_in"))
      (node (ref "U1") (pin "79") (pinfunction "AVSS1_79") (pintype "power_in"))
      (node (ref "U10") (pin "3") (pinfunction "GND_3") (pintype "power_in"))
      (node (ref "U10") (pin "6") (pinfunction "GND_6") (pintype "power_in"))
      (node (ref "U11") (pin "3") (pinfunction "GND_3") (pintype "power_in"))
      (node (ref "U11") (pin "6") (pinfunction "GND_6") (pintype "power_in"))
      (node (ref "U12") (pin "4") (pinfunction "GND_4") (pintype "passive"))
      (node (ref "U13") (pin "5") (pinfunction "GND_5") (pintype "power_in"))
      (node (ref "U2") (pin "1") (pinfunction "A1_1") (pintype "input"))
      (node (ref "U2") (pin "2") (pinfunction "A0_2") (pintype "input"))
      (node (ref "U2") (pin "7") (pinfunction "GND_7") (pintype "power_in"))
      (node (ref "U3") (pin "3") (pinfunction "GND_3") (pintype "power_in"))
      (node (ref "U3") (pin "4") (pinfunction "CSB_4") (pintype "input"))
      (node (ref "U3") (pin "5") (pinfunction "CSB_5") (pintype "input"))
      (node (ref "U4") (pin "4") (pinfunction "GND_4") (pintype "power_in"))
      (node (ref "U5") (pin "4") (pinfunction "GND_4") (pintype "passive"))
      (node (ref "U5") (pin "5") (pinfunction "A2_5") (pintype "passive"))
      (node (ref "U5") (pin "6") (pinfunction "A1_6") (pintype "passive"))
      (node (ref "U5") (pin "7") (pinfunction "A0_7") (pintype "passive"))
      (node (ref "U6") (pin "2") (pinfunction "GND_2") (pintype "power_in"))
      (node (ref "U6") (pin "4") (pinfunction "GND_4") (pintype "power_in"))
      (node (ref "U6") (pin "5") (pinfunction "GND_5") (pintype "power_in"))
      (node (ref "U7") (pin "10") (pinfunction "VSS_10") (pintype "power_in"))
      (node (ref "U8") (pin "3") (pinfunction "GND_3") (pintype "power_in"))
      (node (ref "U8") (pin "6") (pinfunction "GND_6") (pintype "power_in"))
      (node (ref "U9") (pin "3") (pinfunction "GND_3") (pintype "power_in"))
      (node (ref "U9") (pin "6") (pinfunction "GND_6") (pintype "power_in"))
    )
    (net (code "57") (name "Net-(D1-K)") (class "Default")
      (node (ref "D1") (pin "4") (pinfunction "K_4") (pintype "passive"))
      (node (ref "L1") (pin "2") (pinfunction "2_2") (pintype "passive"))
      (node (ref "U8") (pin "2") (pinfunction "VOUT_2") (pintype "power_in"))
    )
    (net (code "58") (name "Net-(D2-K)") (class "Default")
      (node (ref "D2") (pin "4") (pinfunction "K_4") (pintype "passive"))
      (node (ref "L2") (pin "2") (pinfunction "2_2") (pintype "passive"))
      (node (ref "U9") (pin "2") (pinfunction "VOUT_2") (pintype "power_in"))
    )
    (net (code "59") (name "Net-(D3-A)") (class "Default")
      (node (ref "D3") (pin "2") (pinfunction "A_2") (pintype "passive"))
      (node (ref "R12") (pin "1") (pinfunction "1_1") (pintype "passive"))
    )
    (net (code "60") (name "Net-(D4-K)") (class "Default")
      (node (ref "D4") (pin "4") (pinfunction "K_4") (pintype "passive"))
      (node (ref "L3") (pin "2") (pinfunction "2_2") (pintype "passive"))
      (node (ref "U10") (pin "2") (pinfunction "VOUT_2") (pintype "power_in"))
    )
    (net (code "61") (name "Net-(D5-K)") (class "Default")
      (node (ref "D5") (pin "4") (pinfunction "K_4") (pintype "passive"))
      (node (ref "L4") (pin "2") (pinfunction "2_2") (pintype "passive"))
      (node (ref "U11") (pin "2") (pinfunction "VOUT_2") (pintype "power_in"))
    )
    (net (code "62") (name "Net-(P3-Pad5)") (class "Default")
      (node (ref "P3") (pin "5") (pinfunction "5_5") (pintype "passive"))
      (node (ref "R16") (pin "2") (pinfunction "2_2") (pintype "passive"))
    )
    (net (code "63") (name "Net-(P3-Pad6)") (class "Default")
      (node (ref "P3") (pin "6") (pinfunction "6_6") (pintype "passive"))
      (node (ref "R17") (pin "2") (pinfunction "2_2") (pintype "passive"))
    )
    (net (code "64") (name "Net-(P4-Pad5)") (class "Default")
      (node (ref "P4") (pin "5") (pinfunction "5_5") (pintype "passive"))
      (node (ref "R18") (pin "2") (pinfunction "2_2") (pintype "passive"))
    )
    (net (code "65") (name "Net-(P4-Pad6)") (class "Default")
      (node (ref "P4") (pin "6") (pinfunction "6_6") (pintype "passive"))
      (node (ref "R19") (pin "2") (pinfunction "2_2") (pintype "passive"))
    )
    (net (code "66") (name "Net-(P5-Pad5)") (class "Default")
      (node (ref "P5") (pin "5") (pinfunction "5_5") (pintype "passive"))
      (node (ref "R20") (pin "2") (pinfunction "2_2") (pintype "passive"))
    )
    (net (code "67") (name "Net-(P5-Pad6)") (class "Default")
      (node (ref "P5") (pin "6") (pinfunction "6_6") (pintype "passive"))
      (node (ref "R21") (pin "2") (pinfunction "2_2") (pintype "passive"))
    )
    (net (code "68") (name "Net-(P7-Pad2)") (class "Default")
      (node (ref "P7") (pin "2") (pinfunction "2_2") (pintype "passive"))
      (node (ref "P8") (pin "1") (pinfunction "1_1") (pintype "passive"))
    )
    (net (code "69") (name "Net-(P7-Pad4)") (class "Default")
      (node (ref "P7") (pin "4") (pinfunction "4_4") (pintype "passive"))
      (node (ref "P8") (pin "3") (pinfunction "3_3") (pintype "passive"))
    )
    (net (code "70") (name "Net-(P12-Pad5)") (class "Default")
      (node (ref "P12") (pin "5") (pinfunction "5_5") (pintype "passive"))
      (node (ref "R27") (pin "2") (pinfunction "2_2") (pintype "passive"))
    )
    (net (code "71") (name "Net-(P12-Pad6)") (class "Default")
      (node (ref "P12") (pin "6") (pinfunction "6_6") (pintype "passive"))
      (node (ref "R28") (pin "2") (pinfunction "2_2") (pintype "passive"))
    )
    (net (code "72") (name "Net-(U1-AVCC1)") (class "Default")
      (node (ref "C20") (pin "1") (pinfunction "1_1") (pintype "passive"))
      (node (ref "R11") (pin "2") (pinfunction "2_2") (pintype "passive"))
      (node (ref "U1") (pin "80") (pinfunction "AVCC1_80") (pintype "power_in"))
    )
    (net (code "73") (name "Net-(U1-P1.0{slash}TA0.1{slash}DMAE0{slash}RTCCLK{slash}A0{slash}C0{slash}VREF-{slash}VeREF)") (class "Default")
      (node (ref "R12") (pin "2") (pinfunction "2_2") (pintype "passive"))
      (node (ref "U1") (pin "1") (pinfunction "P1.0/TA0.1/DMAE0/RTCCLK/A0/C0/VREF-/VeREF_1") (pintype "bidirectional"))
    )
    (net (code "74") (name "Net-(U1-P2.0{slash}TB0.6{slash}UCA0TXD{slash}UCA0SIMO{slash}TB0CLK{slash}ACLK)") (class "Default")
      (node (ref "R15") (pin "1") (pinfunction "1_1") (pintype "passive"))
      (node (ref "U1") (pin "41") (pinfunction "P2.0/TB0.6/UCA0TXD/UCA0SIMO/TB0CLK/ACLK_41") (pintype "bidirectional"))
    )
    (net (code "75") (name "Net-(U1-P2.1{slash}TB0.0{slash}UCA0RXD{slash}UCA0SOMI)") (class "Default")
      (node (ref "R14") (pin "1") (pinfunction "1_1") (pintype "passive"))
      (node (ref "U1") (pin "42") (pinfunction "P2.1/TB0.0/UCA0RXD/UCA0SOMI_42") (pintype "bidirectional"))
    )
    (net (code "76") (name "Net-(U2-IN+)") (class "Default")
      (node (ref "C3") (pin "1") (pinfunction "1_1") (pintype "passive"))
      (node (ref "R5") (pin "1") (pinfunction "1_1") (pintype "passive"))
      (node (ref "U2") (pin "10") (pinfunction "IN+_10") (pintype "input"))
    )
    (net (code "77") (name "Net-(U2-IN-)") (class "Default")
      (node (ref "C3") (pin "2") (pinfunction "2_2") (pintype "passive"))
      (node (ref "R6") (pin "1") (pinfunction "1_1") (pintype "passive"))
      (node (ref "U2") (pin "9") (pinfunction "IN-_9") (pintype "input"))
    )
    (net (code "78") (name "Net-(U2-VBUS)") (class "Default")
      (node (ref "P1") (pin "3") (pinfunction "3_3") (pintype "passive"))
      (node (ref "P1") (pin "4") (pinfunction "4_4") (pintype "passive"))
      (node (ref "P1B") (pin "2") (pinfunction "2_2") (pintype "passive"))
      (node (ref "R1") (pin "1") (pinfunction "1_1") (pintype "passive"))
      (node (ref "R5") (pin "2") (pinfunction "2_2") (pintype "passive"))
      (node (ref "U2") (pin "8") (pinfunction "VBUS_8") (pintype "input"))
    )
    (net (code "79") (name "Net-(U4-VBAT)") (class "Default")
      (node (ref "P11") (pin "2") (pinfunction "2_2") (pintype "passive"))
      (node (ref "U4") (pin "3") (pinfunction "VBAT_3") (pintype "power_in"))
    )
    (net (code "80") (name "Net-(U4-X1)") (class "Default")
      (node (ref "U4") (pin "1") (pinfunction "X1_1") (pintype "passive"))
      (node (ref "Y1") (pin "1") (pinfunction "OSC1_1") (pintype "passive"))
    )
    (net (code "81") (name "Net-(U4-X2)") (class "Default")
      (node (ref "U4") (pin "2") (pinfunction "X2_2") (pintype "passive"))
      (node (ref "Y1") (pin "2") (pinfunction "OSC2_2") (pintype "passive"))
    )
    (net (code "82") (name "Net-(U5-ALERT)") (class "Default")
      (node (ref "R4") (pin "2") (pinfunction "2_2") (pintype "passive"))
      (node (ref "U5") (pin "3") (pinfunction "ALERT_3") (pintype "passive"))
    )
    (net (code "83") (name "Net-(U8-FEEDBACK)") (class "Default")
      (node (ref "C30") (pin "2") (pinfunction "2_2") (pintype "passive"))
      (node (ref "R29") (pin "2") (pinfunction "2_2") (pintype "passive"))
      (node (ref "R30") (pin "2") (pinfunction "2_2") (pintype "passive"))
      (node (ref "U8") (pin "4") (pinfunction "FEEDBACK_4") (pintype "input"))
    )
    (net (code "84") (name "Net-(U9-FEEDBACK)") (class "Default")
      (node (ref "C31") (pin "2") (pinfunction "2_2") (pintype "passive"))
      (node (ref "R31") (pin "2") (pinfunction "2_2") (pintype "passive"))
      (node (ref "R32") (pin "2") (pinfunction "2_2") (pintype "passive"))
      (node (ref "U9") (pin "4") (pinfunction "FEEDBACK_4") (pintype "input"))
    )
    (net (code "85") (name "Net-(U10-FEEDBACK)") (class "Default")
      (node (ref "C32") (pin "2") (pinfunction "2_2") (pintype "passive"))
      (node (ref "R33") (pin "2") (pinfunction "2_2") (pintype "passive"))
      (node (ref "R34") (pin "2") (pinfunction "2_2") (pintype "passive"))
      (node (ref "U10") (pin "4") (pinfunction "FEEDBACK_4") (pintype "input"))
    )
    (net (code "86") (name "Net-(U11-FEEDBACK)") (class "Default")
      (node (ref "C33") (pin "2") (pinfunction "2_2") (pintype "passive"))
      (node (ref "R35") (pin "2") (pinfunction "2_2") (pintype "passive"))
      (node (ref "R36") (pin "2") (pinfunction "2_2") (pintype "passive"))
      (node (ref "U11") (pin "4") (pinfunction "FEEDBACK_4") (pintype "input"))
    )
    (net (code "87") (name "VBat") (class "Default")
      (node (ref "C14") (pin "1") (pinfunction "1_1") (pintype "passive"))
      (node (ref "C15") (pin "1") (pinfunction "1_1") (pintype "passive"))
      (node (ref "C21") (pin "1") (pinfunction "1_1") (pintype "passive"))
      (node (ref "C22") (pin "1") (pinfunction "1_1") (pintype "passive"))
      (node (ref "C27") (pin "1") (pinfunction "1_1") (pintype "passive"))
      (node (ref "C28") (pin "1") (pinfunction "1_1") (pintype "passive"))
      (node (ref "C4") (pin "1") (pinfunction "1_1") (pintype "passive"))
      (node (ref "C5") (pin "1") (pinfunction "1_1") (pintype "passive"))
      (node (ref "C9") (pin "2") (pinfunction "2_2") (pintype "passive"))
      (node (ref "R1") (pin "2") (pinfunction "2_2") (pintype "passive"))
      (node (ref "R6") (pin "2") (pinfunction "2_2") (pintype "passive"))
      (node (ref "U10") (pin "1") (pinfunction "VIN_1") (pintype "power_in"))
      (node (ref "U11") (pin "1") (pinfunction "VIN_1") (pintype "power_in"))
      (node (ref "U12") (pin "1") (pinfunction "VCC_1") (pintype "power_in"))
      (node (ref "U8") (pin "1") (pinfunction "VIN_1") (pintype "power_in"))
      (node (ref "U9") (pin "1") (pinfunction "VIN_1") (pintype "power_in"))
    )
    (net (code "88") (name "unconnected-(FID1-Pad0)") (class "Default")
      (node (ref "FID1") (pin "0") (pinfunction "0_0") (pintype "passive"))
    )
    (net (code "89") (name "unconnected-(FID2-Pad0)") (class "Default")
      (node (ref "FID2") (pin "0") (pinfunction "0_0") (pintype "passive"))
    )
    (net (code "90") (name "unconnected-(FID3-Pad0)") (class "Default")
      (node (ref "FID3") (pin "0") (pinfunction "0_0") (pintype "passive"))
    )
    (net (code "91") (name "unconnected-(P6-Pad2)") (class "Default")
      (node (ref "P6") (pin "2") (pinfunction "2_2") (pintype "passive+no_connect"))
    )
    (net (code "92") (name "unconnected-(P6-Pad3)") (class "Default")
      (node (ref "P6") (pin "3") (pinfunction "3_3") (pintype "passive+no_connect"))
    )
    (net (code "93") (name "unconnected-(P6-Pad6)") (class "Default")
      (node (ref "P6") (pin "6") (pinfunction "6_6") (pintype "passive+no_connect"))
    )
    (net (code "94") (name "unconnected-(P7-Pad6)") (class "Default")
      (node (ref "P7") (pin "6") (pinfunction "6_6") (pintype "passive+no_connect"))
    )
    (net (code "95") (name "unconnected-(P7-Pad10)") (class "Default")
      (node (ref "P7") (pin "10") (pinfunction "10_10") (pintype "passive+no_connect"))
    )
    (net (code "96") (name "unconnected-(P7-Pad12)") (class "Default")
      (node (ref "P7") (pin "12") (pinfunction "12_12") (pintype "passive+no_connect"))
    )
    (net (code "97") (name "unconnected-(P7-Pad13)") (class "Default")
      (node (ref "P7") (pin "13") (pinfunction "13_13") (pintype "passive+no_connect"))
    )
    (net (code "98") (name "unconnected-(P7-Pad14)") (class "Default")
      (node (ref "P7") (pin "14") (pinfunction "14_14") (pintype "passive+no_connect"))
    )
    (net (code "99") (name "unconnected-(U1-P1.1{slash}TA0.2{slash}TA1CLK{slash}COUT{slash}A1{slash}C1{slash}VREF+{slash}VeREF+-Pad2)") (class "Default")
      (node (ref "U1") (pin "2") (pinfunction "P1.1/TA0.2/TA1CLK/COUT/A1/C1/VREF+/VeREF+_2") (pintype "bidirectional+no_connect"))
    )
    (net (code "100") (name "unconnected-(U1-P1.2{slash}TA1.1{slash}TA0CLK{slash}COUT{slash}A2{slash}C2-Pad3)") (class "Default")
      (node (ref "U1") (pin "3") (pinfunction "P1.2/TA1.1/TA0CLK/COUT/A2/C2_3") (pintype "bidirectional+no_connect"))
    )
    (net (code "101") (name "unconnected-(U1-P1.3{slash}TA1.2{slash}UCB0STE{slash}A3{slash}C3-Pad16)") (class "Default")
      (node (ref "U1") (pin "16") (pinfunction "P1.3/TA1.2/UCB0STE/A3/C3_16") (pintype "bidirectional+no_connect"))
    )
    (net (code "102") (name "unconnected-(U1-P1.4{slash}TB0.1{slash}UCA0STE{slash}A4{slash}C4-Pad17)") (class "Default")
      (node (ref "U1") (pin "17") (pinfunction "P1.4/TB0.1/UCA0STE/A4/C4_17") (pintype "bidirectional+no_connect"))
    )
    (net (code "103") (name "unconnected-(U1-P1.5{slash}TB0.2{slash}UCA0CLK{slash}A5{slash}C5-Pad18)") (class "Default")
      (node (ref "U1") (pin "18") (pinfunction "P1.5/TB0.2/UCA0CLK/A5/C5_18") (pintype "bidirectional+no_connect"))
    )
    (net (code "104") (name "unconnected-(U1-P3.0{slash}A12{slash}C12-Pad4)") (class "Default")
      (node (ref "U1") (pin "4") (pinfunction "P3.0/A12/C12_4") (pintype "bidirectional+no_connect"))
    )
    (net (code "105") (name "unconnected-(U1-P3.1{slash}A13{slash}C13-Pad5)") (class "Default")
      (node (ref "U1") (pin "5") (pinfunction "P3.1/A13/C13_5") (pintype "bidirectional+no_connect"))
    )
    (net (code "106") (name "unconnected-(U1-P3.2{slash}A14{slash}C14-Pad6)") (class "Default")
      (node (ref "U1") (pin "6") (pinfunction "P3.2/A14/C14_6") (pintype "bidirectional+no_connect"))
    )
    (net (code "107") (name "unconnected-(U1-P3.3{slash}A15{slash}C15-Pad7)") (class "Default")
      (node (ref "U1") (pin "7") (pinfunction "P3.3/A15/C15_7") (pintype "bidirectional+no_connect"))
    )
    (net (code "108") (name "unconnected-(U1-P4.3{slash}A11-Pad34)") (class "Default")
      (node (ref "U1") (pin "34") (pinfunction "P4.3/A11_34") (pintype "bidirectional+no_connect"))
    )
    (net (code "109") (name "unconnected-(U1-P4.7-Pad12)") (class "Default")
      (node (ref "U1") (pin "12") (pinfunction "P4.7_12") (pintype "bidirectional+no_connect"))
    )
    (net (code "110") (name "unconnected-(U1-P6.2{slash}UCA3CLK-Pad10)") (class "Default")
      (node (ref "U1") (pin "10") (pinfunction "P6.2/UCA3CLK_10") (pintype "bidirectional+no_connect"))
    )
    (net (code "111") (name "unconnected-(U1-P6.3{slash}UCA3STE-Pad11)") (class "Default")
      (node (ref "U1") (pin "11") (pinfunction "P6.3/UCA3STE_11") (pintype "bidirectional+no_connect"))
    )
    (net (code "112") (name "unconnected-(U1-P6.4{slash}UCB3SIMO{slash}UCB3SDA-Pad69)") (class "Default")
      (node (ref "U1") (pin "69") (pinfunction "P6.4/UCB3SIMO/UCB3SDA_69") (pintype "bidirectional+no_connect"))
    )
    (net (code "113") (name "unconnected-(U1-P6.5{slash}UCB3SOMI{slash}UCB3SCL-Pad70)") (class "Default")
      (node (ref "U1") (pin "70") (pinfunction "P6.5/UCB3SOMI/UCB3SCL_70") (pintype "bidirectional+no_connect"))
    )
    (net (code "114") (name "unconnected-(U1-P6.6{slash}UCB3CLK-Pad71)") (class "Default")
      (node (ref "U1") (pin "71") (pinfunction "P6.6/UCB3CLK_71") (pintype "bidirectional+no_connect"))
    )
    (net (code "115") (name "unconnected-(U1-P6.7{slash}UCB3STE-Pad72)") (class "Default")
      (node (ref "U1") (pin "72") (pinfunction "P6.7/UCB3STE_72") (pintype "bidirectional+no_connect"))
    )
    (net (code "116") (name "unconnected-(U1-P7.2{slash}UCB2CLK-Pad25)") (class "Default")
      (node (ref "U1") (pin "25") (pinfunction "P7.2/UCB2CLK_25") (pintype "bidirectional+no_connect"))
    )
    (net (code "117") (name "unconnected-(U1-P7.3{slash}UCB2STE{slash}TA4.1-Pad26)") (class "Default")
      (node (ref "U1") (pin "26") (pinfunction "P7.3/UCB2STE/TA4.1_26") (pintype "bidirectional+no_connect"))
    )
    (net (code "118") (name "unconnected-(U1-P7.4{slash}{slash}TA4.0{slash}A16-Pad27)") (class "Default")
      (node (ref "U1") (pin "27") (pinfunction "P7.4//TA4.0/A16_27") (pintype "bidirectional+no_connect"))
    )
    (net (code "119") (name "unconnected-(U1-P8.0-Pad15)") (class "Default")
      (node (ref "U1") (pin "15") (pinfunction "P8.0_15") (pintype "bidirectional+no_connect"))
    )
    (net (code "120") (name "unconnected-(U1-P8.1-Pad44)") (class "Default")
      (node (ref "U1") (pin "44") (pinfunction "P8.1_44") (pintype "bidirectional+no_connect"))
    )
    (net (code "121") (name "unconnected-(U1-PJ.6{slash}HFXIN-Pad74)") (class "Default")
      (node (ref "U1") (pin "74") (pinfunction "PJ.6/HFXIN_74") (pintype "input+no_connect"))
    )
    (net (code "122") (name "unconnected-(U1-PJ.7{slash}HFXOUT-Pad75)") (class "Default")
      (node (ref "U1") (pin "75") (pinfunction "PJ.7/HFXOUT_75") (pintype "input+no_connect"))
    )
    (net (code "123") (name "unconnected-(U3-SDO-Pad6)") (class "Default")
      (node (ref "U3") (pin "6") (pinfunction "SDO_6") (pintype "output+no_connect"))
    )
    (net (code "124") (name "unconnected-(U4-SQW{slash}OUT-Pad7)") (class "Default")
      (node (ref "U4") (pin "7") (pinfunction "SQW/OUT_7") (pintype "output+no_connect"))
    )
    (net (code "125") (name "unconnected-(U6-INT2-Pad9)") (class "Default")
      (node (ref "U6") (pin "9") (pinfunction "INT2_9") (pintype "output+no_connect"))
    )
    (net (code "126") (name "unconnected-(U6-NC-Pad10)") (class "Default")
      (node (ref "U6") (pin "10") (pinfunction "NC_10") (pintype "passive+no_connect"))
    )
    (net (code "127") (name "unconnected-(U6-RES-Pad3)") (class "Default")
      (node (ref "U6") (pin "3") (pinfunction "RES_3") (pintype "passive+no_connect"))
    )
    (net (code "128") (name "unconnected-(U6-RES-Pad11)") (class "Default")
      (node (ref "U6") (pin "11") (pinfunction "RES_11") (pintype "passive+no_connect"))
    )
    (net (code "129") (name "unconnected-(U7-DNU-Pad4)") (class "Default")
      (node (ref "U7") (pin "4") (pinfunction "DNU_4") (pintype "passive+no_connect"))
    )
    (net (code "130") (name "unconnected-(U7-DNU-Pad5)") (class "Default")
      (node (ref "U7") (pin "5") (pinfunction "DNU_5") (pintype "passive+no_connect"))
    )
    (net (code "131") (name "unconnected-(U7-DNU-Pad11)") (class "Default")
      (node (ref "U7") (pin "11") (pinfunction "DNU_11") (pintype "passive+no_connect"))
    )
    (net (code "132") (name "unconnected-(U7-DNU-Pad12)") (class "Default")
      (node (ref "U7") (pin "12") (pinfunction "DNU_12") (pintype "passive+no_connect"))
    )
    (net (code "133") (name "unconnected-(U7-HOLD#{slash}IO3-Pad1)") (class "Default")
      (node (ref "U7") (pin "1") (pinfunction "HOLD#/IO3_1") (pintype "input+no_connect"))
    )
    (net (code "134") (name "unconnected-(U7-NC-Pad13)") (class "Default")
      (node (ref "U7") (pin "13") (pinfunction "NC_13") (pintype "passive+no_connect"))
    )
    (net (code "135") (name "unconnected-(U7-RESET#-Pad3)") (class "Default")
      (node (ref "U7") (pin "3") (pinfunction "RESET#_3") (pintype "input+no_connect"))
    )
    (net (code "136") (name "unconnected-(U7-VIO{slash}RFU-Pad14)") (class "Default")
      (node (ref "U7") (pin "14") (pinfunction "VIO/RFU_14") (pintype "power_in+no_connect"))
    )
    (net (code "137") (name "unconnected-(U7-WP#{slash}IO2-Pad9)") (class "Default")
      (node (ref "U7") (pin "9") (pinfunction "WP#/IO2_9") (pintype "input+no_connect"))
    )
    (net (code "138") (name "unconnected-(U12-NC-Pad2)") (class "Default")
      (node (ref "U12") (pin "2") (pinfunction "NC_2") (pintype "passive+no_connect"))
    )
  )
)
